# MyNixie.net
KiCad netlist of a schematic drawn in Altium Designer
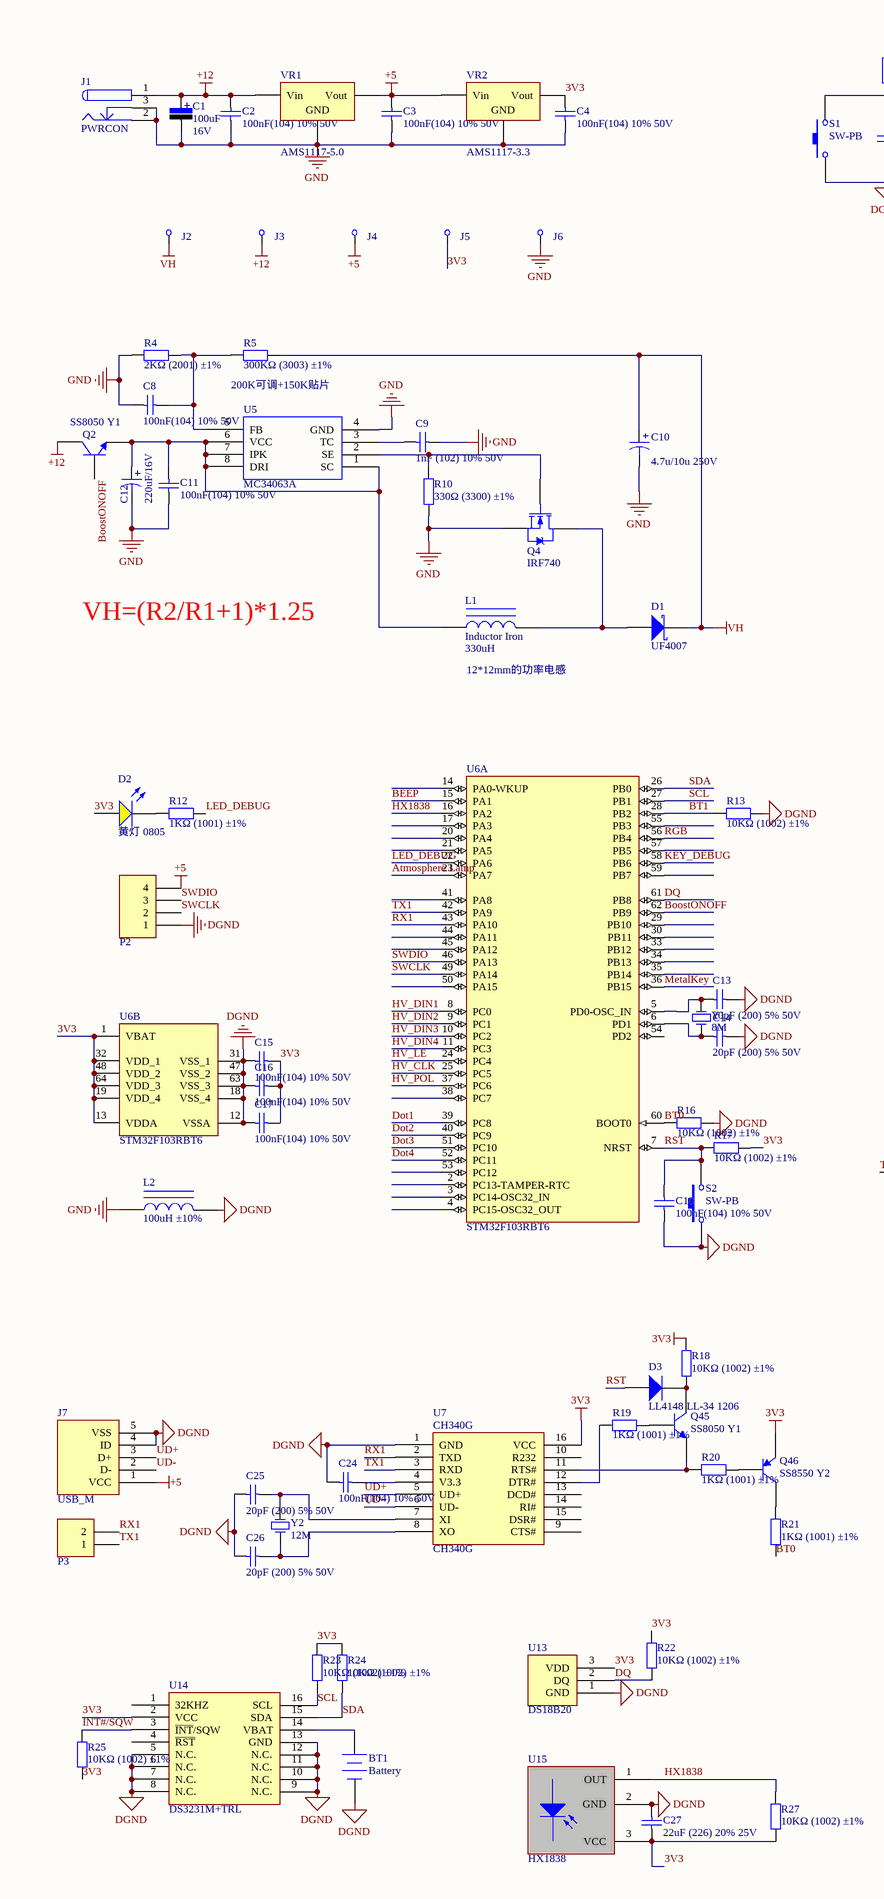
[diagram p0: MyNixie.SchDoc, left]
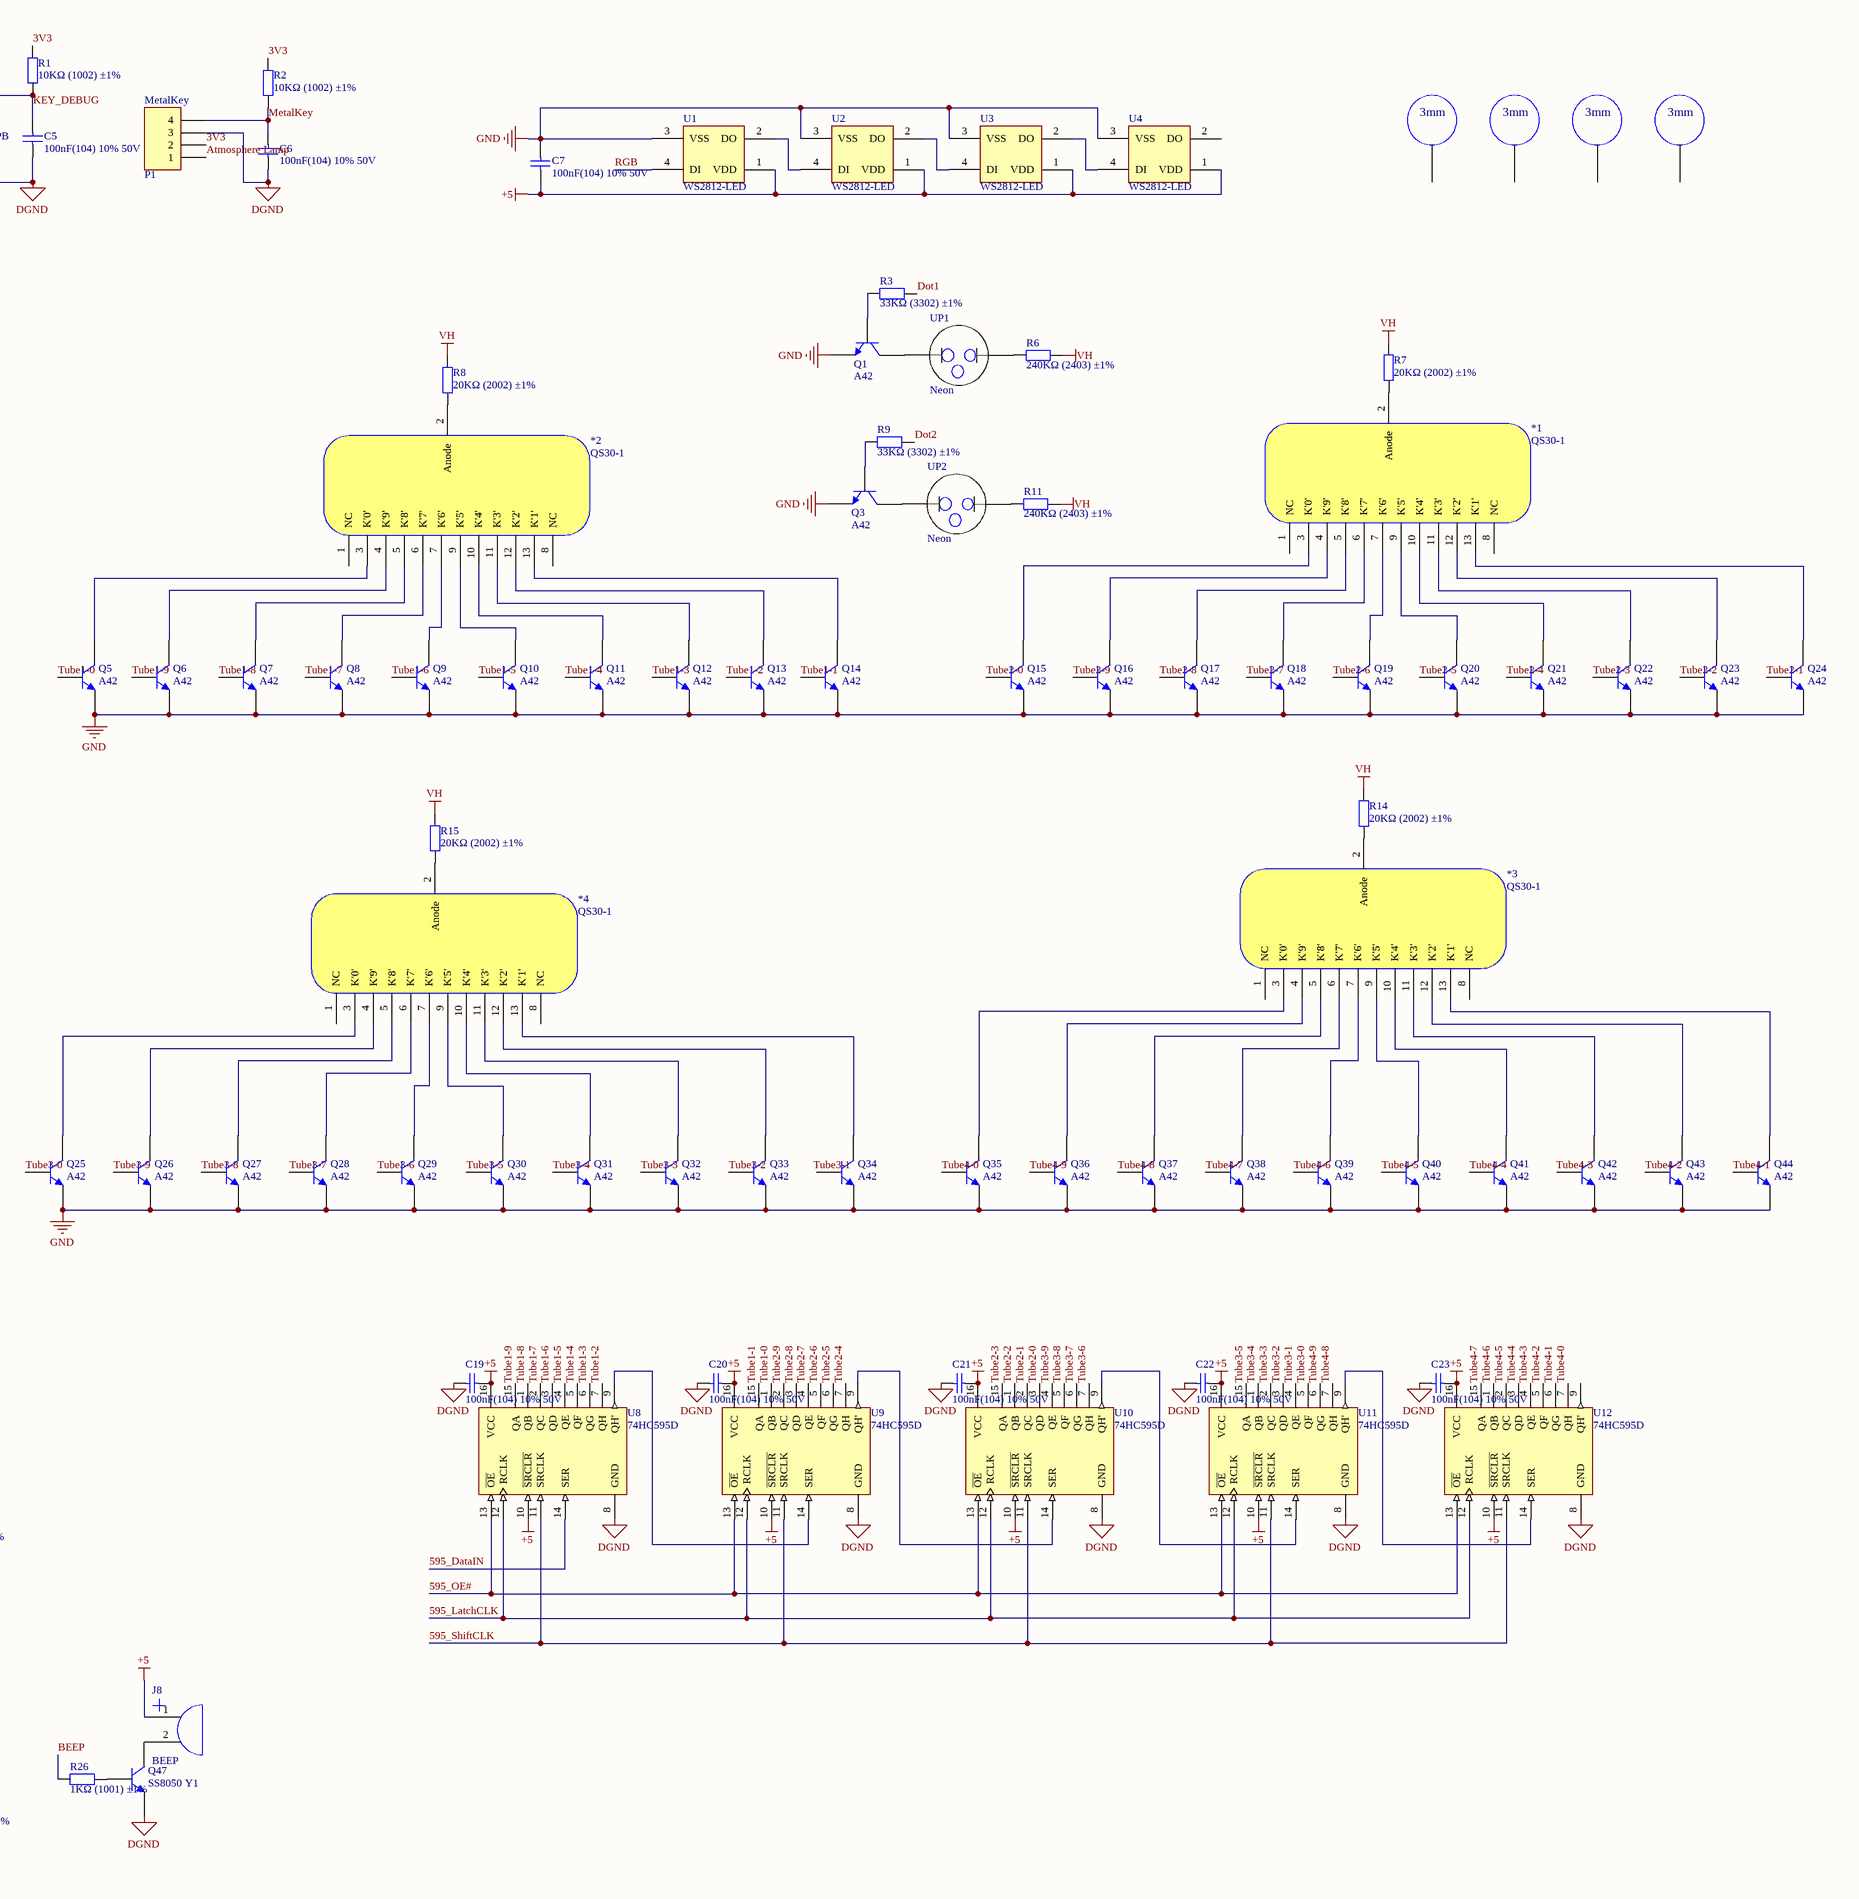
[diagram p1: MyNixie.SchDoc, right]

(export (version "E")
  (design (tool "Eeschema 10.0.6"))
  (components
    (comp (ref "*1")
      (value "QS30-1")
      (footprint "QS30-1")
      (description "南昌辉光管")
      (libsource (lib "fszhang") (part "QS30-1"))
    )
    (comp (ref "*2")
      (value "QS30-1")
      (footprint "QS30-1")
      (description "南昌辉光管")
      (libsource (lib "fszhang") (part "QS30-1"))
    )
    (comp (ref "*3")
      (value "QS30-1")
      (footprint "QS30-1")
      (description "南昌辉光管")
      (libsource (lib "fszhang") (part "QS30-1"))
    )
    (comp (ref "*4")
      (value "QS30-1")
      (footprint "QS30-1")
      (description "南昌辉光管")
      (libsource (lib "fszhang") (part "QS30-1"))
    )
    (comp (ref "BT1")
      (value "Battery")
      (footprint "CR1220")
      (description "备份电池")
      (fields (field (name "PUBLISHER") "Altium Limited"))
      (libsource (lib "fszhang") (part "Battery"))
    )
    (comp (ref "C1")
      (value "100uF")
      (footprint "C-RB-10")
      (description "极性电解电容")
      (fields
        (field (name "VOL") "16V")
        (field (name "Comment") "Cap Pol")
        (field (name "PUBLISHER") "Altium Limited")
      )
      (libsource (lib "fszhang") (part "Cap Pol"))
    )
    (comp (ref "C2")
      (value "100nF(104) 10% 50V")
      (footprint "LC-0805_C")
      (description "贴片电容")
      (libsource (lib "Miscellaneous Devices LC") (part "0805 100nF(104) 10% 50V"))
    )
    (comp (ref "C3")
      (value "100nF(104) 10% 50V")
      (footprint "LC-0805_C")
      (description "贴片电容")
      (libsource (lib "Miscellaneous Devices LC") (part "0805 100nF(104) 10% 50V"))
    )
    (comp (ref "C4")
      (value "100nF(104) 10% 50V")
      (footprint "LC-0805_C")
      (description "贴片电容")
      (libsource (lib "Miscellaneous Devices LC") (part "0805 100nF(104) 10% 50V"))
    )
    (comp (ref "C5")
      (value "100nF(104) 10% 50V")
      (footprint "LC-0805_C")
      (description "贴片电容")
      (libsource (lib "Miscellaneous Devices LC") (part "0805 100nF(104) 10% 50V"))
    )
    (comp (ref "C6")
      (value "100nF(104) 10% 50V")
      (footprint "LC-0805_C")
      (description "贴片电容")
      (libsource (lib "Miscellaneous Devices LC") (part "0805 100nF(104) 10% 50V"))
    )
    (comp (ref "C7")
      (value "100nF(104) 10% 50V")
      (footprint "LC-0805_C")
      (description "贴片电容")
      (libsource (lib "Miscellaneous Devices LC") (part "0805 100nF(104) 10% 50V"))
    )
    (comp (ref "C8")
      (value "100nF(104) 10% 50V")
      (footprint "LC-0805_C")
      (description "贴片电容")
      (libsource (lib "Miscellaneous Devices LC") (part "0805 100nF(104) 10% 50V"))
    )
    (comp (ref "C9")
      (value "1nF (102) 10% 50V")
      (footprint "LC-0805_C")
      (description "贴片电容")
      (libsource (lib "Miscellaneous Devices LC") (part "0805 1nF (102) 10% 50V"))
    )
    (comp (ref "C10")
      (value "4.7u/10u 250V")
      (footprint "C-RB-10")
      (description "Polarized Capacitor (Radial)")
      (fields (field (name "Comment") "Cap Pol1") (field (name "PUBLISHER") "Altium Limited"))
      (libsource (lib "Miscellaneous Devices") (part "Cap Pol1"))
    )
    (comp (ref "C11")
      (value "100nF(104) 10% 50V")
      (footprint "LC-0805_C")
      (description "贴片电容")
      (libsource (lib "Miscellaneous Devices LC") (part "0805 100nF(104) 10% 50V"))
    )
    (comp (ref "C12")
      (value "220uF/16V")
      (footprint "C-RB-6")
      (description "Polarized Capacitor (Radial)")
      (fields (field (name "Comment") "Cap Pol1") (field (name "PUBLISHER") "Altium Limited"))
      (libsource (lib "Miscellaneous Devices") (part "Cap Pol1"))
    )
    (comp (ref "C13")
      (value "20pF (200) 5% 50V")
      (footprint "LC-0805_C")
      (description "贴片电容")
      (libsource (lib "Miscellaneous Devices LC") (part "0805 20pF (200) 5% 50V"))
    )
    (comp (ref "C14")
      (value "20pF (200) 5% 50V")
      (footprint "LC-0805_C")
      (description "贴片电容")
      (libsource (lib "Miscellaneous Devices LC") (part "0805 20pF (200) 5% 50V"))
    )
    (comp (ref "C15")
      (value "100nF(104) 10% 50V")
      (footprint "LC-0805_C")
      (description "贴片电容")
      (libsource (lib "Miscellaneous Devices LC") (part "0805 100nF(104) 10% 50V"))
    )
    (comp (ref "C16")
      (value "100nF(104) 10% 50V")
      (footprint "LC-0805_C")
      (description "贴片电容")
      (libsource (lib "Miscellaneous Devices LC") (part "0805 100nF(104) 10% 50V"))
    )
    (comp (ref "C17")
      (value "100nF(104) 10% 50V")
      (footprint "LC-0805_C")
      (description "贴片电容")
      (libsource (lib "Miscellaneous Devices LC") (part "0805 100nF(104) 10% 50V"))
    )
    (comp (ref "C18")
      (value "100nF(104) 10% 50V")
      (footprint "LC-0805_C")
      (description "贴片电容")
      (libsource (lib "Miscellaneous Devices LC") (part "0805 100nF(104) 10% 50V"))
    )
    (comp (ref "C19")
      (value "100nF(104) 10% 50V")
      (footprint "LC-0805_C")
      (description "贴片电容")
      (libsource (lib "Miscellaneous Devices LC") (part "0805 100nF(104) 10% 50V"))
    )
    (comp (ref "C20")
      (value "100nF(104) 10% 50V")
      (footprint "LC-0805_C")
      (description "贴片电容")
      (libsource (lib "Miscellaneous Devices LC") (part "0805 100nF(104) 10% 50V"))
    )
    (comp (ref "C21")
      (value "100nF(104) 10% 50V")
      (footprint "LC-0805_C")
      (description "贴片电容")
      (libsource (lib "Miscellaneous Devices LC") (part "0805 100nF(104) 10% 50V"))
    )
    (comp (ref "C22")
      (value "100nF(104) 10% 50V")
      (footprint "LC-0805_C")
      (description "贴片电容")
      (libsource (lib "Miscellaneous Devices LC") (part "0805 100nF(104) 10% 50V"))
    )
    (comp (ref "C23")
      (value "100nF(104) 10% 50V")
      (footprint "LC-0805_C")
      (description "贴片电容")
      (libsource (lib "Miscellaneous Devices LC") (part "0805 100nF(104) 10% 50V"))
    )
    (comp (ref "C24")
      (value "100nF(104) 10% 50V")
      (footprint "LC-0805_C")
      (description "贴片电容")
      (libsource (lib "Miscellaneous Devices LC") (part "0805 100nF(104) 10% 50V"))
    )
    (comp (ref "C25")
      (value "20pF (200) 5% 50V")
      (footprint "LC-0805_C")
      (description "贴片电容")
      (libsource (lib "Miscellaneous Devices LC") (part "0805 20pF (200) 5% 50V"))
    )
    (comp (ref "C26")
      (value "20pF (200) 5% 50V")
      (footprint "LC-0805_C")
      (description "贴片电容")
      (libsource (lib "Miscellaneous Devices LC") (part "0805 20pF (200) 5% 50V"))
    )
    (comp (ref "C27")
      (value "22uF (226) 20% 25V")
      (footprint "LC-0805_C")
      (description "贴片电容")
      (libsource (lib "Miscellaneous Devices LC") (part "0805 22uF (226) 20% 25V"))
    )
    (comp (ref "D1")
      (value "UF4007")
      (footprint "DO-41")
      (description "Schottky Diode")
      (fields (field (name "PUBLISHER") "Altium Limited"))
      (libsource (lib "Miscellaneous Devices") (part "D Schottky"))
    )
    (comp (ref "D2")
      (value "黄灯 0805")
      (footprint "LC-0805_LED_S1")
      (description "发光二极管")
      (libsource (lib "Miscellaneous Devices LC") (part "0805 黄灯"))
    )
    (comp (ref "D3")
      (value "LL4148 LL-34 1206")
      (footprint "LC-LL-34")
      (description "开关二极管")
      (libsource (lib "Miscellaneous Devices LC") (part "LL-34 LL4148 LL-34 1206"))
    )
    (comp (ref "J1")
      (value "PWRCON")
      (footprint "DC-005")
      (description "直流电源端子")
      (fields (field (name "PUBLISHER") "Altium Limited"))
      (libsource (lib "fszhang") (part "PWRCON"))
    )
    (comp (ref "J2")
      (value "CHECK")
      (footprint "CHECK-A")
      (description "测试点")
      (libsource (lib "fszhang") (part "CHECK"))
    )
    (comp (ref "J3")
      (value "CHECK")
      (footprint "CHECK-A")
      (description "测试点")
      (libsource (lib "fszhang") (part "CHECK"))
    )
    (comp (ref "J4")
      (value "CHECK")
      (footprint "CHECK-A")
      (description "测试点")
      (libsource (lib "fszhang") (part "CHECK"))
    )
    (comp (ref "J5")
      (value "CHECK")
      (footprint "CHECK-A")
      (description "测试点")
      (libsource (lib "fszhang") (part "CHECK"))
    )
    (comp (ref "J6")
      (value "CHECK")
      (footprint "CHECK-A")
      (description "测试点")
      (libsource (lib "fszhang") (part "CHECK"))
    )
    (comp (ref "J7")
      (value "USB_M")
      (footprint "USB_MICRO")
      (description "MicroUSB接口")
      (libsource (lib "fszhang") (part "USB_M"))
    )
    (comp (ref "J8")
      (value "BEEP")
      (footprint "Beep")
      (description "蜂鸣器")
      (libsource (lib "fszhang") (part "BEEP"))
    )
    (comp (ref "L1")
      (value "Inductor Iron")
      (footprint "L-SMD-12")
      (description "Magnetic-Core Inductor")
      (fields (field (name "ALTIUM_VALUE") "330uH") (field (name "PUBLISHER") "Altium Limited"))
      (libsource (lib "Miscellaneous Devices") (part "Inductor Iron"))
    )
    (comp (ref "L2")
      (value "100uH ±10%")
      (footprint "LC-0805_L")
      (description "贴片电感")
      (libsource (lib "Miscellaneous Devices LC") (part "0805 100uH 10%"))
    )
    (comp (ref "P1")
      (value "MetalKey")
      (footprint "HDR4X1_A")
      (description "接插件")
      (fields (field (name "PUBLISHER") "Altium Limited"))
      (libsource (lib "fszhang") (part "Header 4"))
    )
    (comp (ref "P2")
      (value "Header 4")
      (footprint "HDR4X1_A")
      (description "接插件")
      (fields (field (name "PUBLISHER") "Altium Limited"))
      (libsource (lib "fszhang") (part "Header 4"))
    )
    (comp (ref "P3")
      (value "Header 2")
      (footprint "HDR2X1_A")
      (description "接插件")
      (fields (field (name "PUBLISHER") "Altium Limited"))
      (libsource (lib "fszhang") (part "Header 2"))
    )
    (comp (ref "Q1")
      (value "A42")
      (footprint "LC-SOT-23(SOT-23-3)")
      (description "三极管")
      (libsource (lib "Miscellaneous Devices LC") (part "SOT-23 SS8050 Y1"))
    )
    (comp (ref "Q2")
      (value "SS8050 Y1")
      (footprint "LC-SOT-23(SOT-23-3)")
      (description "三极管")
      (libsource (lib "Miscellaneous Devices LC") (part "SOT-23 SS8050 Y1"))
    )
    (comp (ref "Q3")
      (value "A42")
      (footprint "LC-SOT-23(SOT-23-3)")
      (description "三极管")
      (libsource (lib "Miscellaneous Devices LC") (part "SOT-23 SS8050 Y1"))
    )
    (comp (ref "Q4")
      (value "IRF740")
      (footprint "TO-220AB")
      (description "N-Channel Power MOSFET")
      (fields (field (name "PUBLISHER") "Altium Limited"))
      (libsource (lib "Miscellaneous Devices") (part "NMOS-2"))
    )
    (comp (ref "Q5")
      (value "A42")
      (footprint "LC-SOT-23(SOT-23-3)")
      (description "三极管")
      (libsource (lib "Miscellaneous Devices LC") (part "SOT-23 SS8050 Y1"))
    )
    (comp (ref "Q6")
      (value "A42")
      (footprint "LC-SOT-23(SOT-23-3)")
      (description "三极管")
      (libsource (lib "Miscellaneous Devices LC") (part "SOT-23 SS8050 Y1"))
    )
    (comp (ref "Q7")
      (value "A42")
      (footprint "LC-SOT-23(SOT-23-3)")
      (description "三极管")
      (libsource (lib "Miscellaneous Devices LC") (part "SOT-23 SS8050 Y1"))
    )
    (comp (ref "Q8")
      (value "A42")
      (footprint "LC-SOT-23(SOT-23-3)")
      (description "三极管")
      (libsource (lib "Miscellaneous Devices LC") (part "SOT-23 SS8050 Y1"))
    )
    (comp (ref "Q9")
      (value "A42")
      (footprint "LC-SOT-23(SOT-23-3)")
      (description "三极管")
      (libsource (lib "Miscellaneous Devices LC") (part "SOT-23 SS8050 Y1"))
    )
    (comp (ref "Q10")
      (value "A42")
      (footprint "LC-SOT-23(SOT-23-3)")
      (description "三极管")
      (libsource (lib "Miscellaneous Devices LC") (part "SOT-23 SS8050 Y1"))
    )
    (comp (ref "Q11")
      (value "A42")
      (footprint "LC-SOT-23(SOT-23-3)")
      (description "三极管")
      (libsource (lib "Miscellaneous Devices LC") (part "SOT-23 SS8050 Y1"))
    )
    (comp (ref "Q12")
      (value "A42")
      (footprint "LC-SOT-23(SOT-23-3)")
      (description "三极管")
      (libsource (lib "Miscellaneous Devices LC") (part "SOT-23 SS8050 Y1"))
    )
    (comp (ref "Q13")
      (value "A42")
      (footprint "LC-SOT-23(SOT-23-3)")
      (description "三极管")
      (libsource (lib "Miscellaneous Devices LC") (part "SOT-23 SS8050 Y1"))
    )
    (comp (ref "Q14")
      (value "A42")
      (footprint "LC-SOT-23(SOT-23-3)")
      (description "三极管")
      (libsource (lib "Miscellaneous Devices LC") (part "SOT-23 SS8050 Y1"))
    )
    (comp (ref "Q15")
      (value "A42")
      (footprint "LC-SOT-23(SOT-23-3)")
      (description "三极管")
      (libsource (lib "Miscellaneous Devices LC") (part "SOT-23 SS8050 Y1"))
    )
    (comp (ref "Q16")
      (value "A42")
      (footprint "LC-SOT-23(SOT-23-3)")
      (description "三极管")
      (libsource (lib "Miscellaneous Devices LC") (part "SOT-23 SS8050 Y1"))
    )
    (comp (ref "Q17")
      (value "A42")
      (footprint "LC-SOT-23(SOT-23-3)")
      (description "三极管")
      (libsource (lib "Miscellaneous Devices LC") (part "SOT-23 SS8050 Y1"))
    )
    (comp (ref "Q18")
      (value "A42")
      (footprint "LC-SOT-23(SOT-23-3)")
      (description "三极管")
      (libsource (lib "Miscellaneous Devices LC") (part "SOT-23 SS8050 Y1"))
    )
    (comp (ref "Q19")
      (value "A42")
      (footprint "LC-SOT-23(SOT-23-3)")
      (description "三极管")
      (libsource (lib "Miscellaneous Devices LC") (part "SOT-23 SS8050 Y1"))
    )
    (comp (ref "Q20")
      (value "A42")
      (footprint "LC-SOT-23(SOT-23-3)")
      (description "三极管")
      (libsource (lib "Miscellaneous Devices LC") (part "SOT-23 SS8050 Y1"))
    )
    (comp (ref "Q21")
      (value "A42")
      (footprint "LC-SOT-23(SOT-23-3)")
      (description "三极管")
      (libsource (lib "Miscellaneous Devices LC") (part "SOT-23 SS8050 Y1"))
    )
    (comp (ref "Q22")
      (value "A42")
      (footprint "LC-SOT-23(SOT-23-3)")
      (description "三极管")
      (libsource (lib "Miscellaneous Devices LC") (part "SOT-23 SS8050 Y1"))
    )
    (comp (ref "Q23")
      (value "A42")
      (footprint "LC-SOT-23(SOT-23-3)")
      (description "三极管")
      (libsource (lib "Miscellaneous Devices LC") (part "SOT-23 SS8050 Y1"))
    )
    (comp (ref "Q24")
      (value "A42")
      (footprint "LC-SOT-23(SOT-23-3)")
      (description "三极管")
      (libsource (lib "Miscellaneous Devices LC") (part "SOT-23 SS8050 Y1"))
    )
    (comp (ref "Q25")
      (value "A42")
      (footprint "LC-SOT-23(SOT-23-3)")
      (description "三极管")
      (libsource (lib "Miscellaneous Devices LC") (part "SOT-23 SS8050 Y1"))
    )
    (comp (ref "Q26")
      (value "A42")
      (footprint "LC-SOT-23(SOT-23-3)")
      (description "三极管")
      (libsource (lib "Miscellaneous Devices LC") (part "SOT-23 SS8050 Y1"))
    )
    (comp (ref "Q27")
      (value "A42")
      (footprint "LC-SOT-23(SOT-23-3)")
      (description "三极管")
      (libsource (lib "Miscellaneous Devices LC") (part "SOT-23 SS8050 Y1"))
    )
    (comp (ref "Q28")
      (value "A42")
      (footprint "LC-SOT-23(SOT-23-3)")
      (description "三极管")
      (libsource (lib "Miscellaneous Devices LC") (part "SOT-23 SS8050 Y1"))
    )
    (comp (ref "Q29")
      (value "A42")
      (footprint "LC-SOT-23(SOT-23-3)")
      (description "三极管")
      (libsource (lib "Miscellaneous Devices LC") (part "SOT-23 SS8050 Y1"))
    )
    (comp (ref "Q30")
      (value "A42")
      (footprint "LC-SOT-23(SOT-23-3)")
      (description "三极管")
      (libsource (lib "Miscellaneous Devices LC") (part "SOT-23 SS8050 Y1"))
    )
    (comp (ref "Q31")
      (value "A42")
      (footprint "LC-SOT-23(SOT-23-3)")
      (description "三极管")
      (libsource (lib "Miscellaneous Devices LC") (part "SOT-23 SS8050 Y1"))
    )
    (comp (ref "Q32")
      (value "A42")
      (footprint "LC-SOT-23(SOT-23-3)")
      (description "三极管")
      (libsource (lib "Miscellaneous Devices LC") (part "SOT-23 SS8050 Y1"))
    )
    (comp (ref "Q33")
      (value "A42")
      (footprint "LC-SOT-23(SOT-23-3)")
      (description "三极管")
      (libsource (lib "Miscellaneous Devices LC") (part "SOT-23 SS8050 Y1"))
    )
    (comp (ref "Q34")
      (value "A42")
      (footprint "LC-SOT-23(SOT-23-3)")
      (description "三极管")
      (libsource (lib "Miscellaneous Devices LC") (part "SOT-23 SS8050 Y1"))
    )
    (comp (ref "Q35")
      (value "A42")
      (footprint "LC-SOT-23(SOT-23-3)")
      (description "三极管")
      (libsource (lib "Miscellaneous Devices LC") (part "SOT-23 SS8050 Y1"))
    )
    (comp (ref "Q36")
      (value "A42")
      (footprint "LC-SOT-23(SOT-23-3)")
      (description "三极管")
      (libsource (lib "Miscellaneous Devices LC") (part "SOT-23 SS8050 Y1"))
    )
    (comp (ref "Q37")
      (value "A42")
      (footprint "LC-SOT-23(SOT-23-3)")
      (description "三极管")
      (libsource (lib "Miscellaneous Devices LC") (part "SOT-23 SS8050 Y1"))
    )
    (comp (ref "Q38")
      (value "A42")
      (footprint "LC-SOT-23(SOT-23-3)")
      (description "三极管")
      (libsource (lib "Miscellaneous Devices LC") (part "SOT-23 SS8050 Y1"))
    )
    (comp (ref "Q39")
      (value "A42")
      (footprint "LC-SOT-23(SOT-23-3)")
      (description "三极管")
      (libsource (lib "Miscellaneous Devices LC") (part "SOT-23 SS8050 Y1"))
    )
    (comp (ref "Q40")
      (value "A42")
      (footprint "LC-SOT-23(SOT-23-3)")
      (description "三极管")
      (libsource (lib "Miscellaneous Devices LC") (part "SOT-23 SS8050 Y1"))
    )
    (comp (ref "Q41")
      (value "A42")
      (footprint "LC-SOT-23(SOT-23-3)")
      (description "三极管")
      (libsource (lib "Miscellaneous Devices LC") (part "SOT-23 SS8050 Y1"))
    )
    (comp (ref "Q42")
      (value "A42")
      (footprint "LC-SOT-23(SOT-23-3)")
      (description "三极管")
      (libsource (lib "Miscellaneous Devices LC") (part "SOT-23 SS8050 Y1"))
    )
    (comp (ref "Q43")
      (value "A42")
      (footprint "LC-SOT-23(SOT-23-3)")
      (description "三极管")
      (libsource (lib "Miscellaneous Devices LC") (part "SOT-23 SS8050 Y1"))
    )
    (comp (ref "Q44")
      (value "A42")
      (footprint "LC-SOT-23(SOT-23-3)")
      (description "三极管")
      (libsource (lib "Miscellaneous Devices LC") (part "SOT-23 SS8050 Y1"))
    )
    (comp (ref "Q45")
      (value "SS8050 Y1")
      (footprint "LC-SOT-23(SOT-23-3)")
      (description "三极管")
      (libsource (lib "Miscellaneous Devices LC") (part "SOT-23 SS8050 Y1"))
    )
    (comp (ref "Q46")
      (value "SS8550 Y2")
      (footprint "LC-SOT-23(SOT-23-3)")
      (description "三极管")
      (libsource (lib "Miscellaneous Devices LC") (part "SOT-23 SS8550 Y2"))
    )
    (comp (ref "Q47")
      (value "SS8050 Y1")
      (footprint "LC-SOT-23(SOT-23-3)")
      (description "三极管")
      (libsource (lib "Miscellaneous Devices LC") (part "SOT-23 SS8050 Y1"))
    )
    (comp (ref "R1")
      (value "10KΩ (1002) ±1%")
      (footprint "LC-0805_R")
      (description "贴片电阻")
      (libsource (lib "") (part "0805 10KΩ (1002) 1%_1"))
    )
    (comp (ref "R2")
      (value "10KΩ (1002) ±1%")
      (footprint "LC-0805_R")
      (description "贴片电阻")
      (libsource (lib "") (part "0805 10KΩ (1002) 1%_1"))
    )
    (comp (ref "R3")
      (value "33KΩ (3302) ±1%")
      (footprint "LC-0805_R")
      (description "贴片电阻")
      (libsource (lib "") (part "0805 33KΩ (3302) 1%_1"))
    )
    (comp (ref "R4")
      (value "2KΩ (2001) ±1%")
      (footprint "LC-0805_R")
      (description "贴片电阻")
      (libsource (lib "Miscellaneous Devices LC") (part "0805 2KΩ (2001) 1%"))
    )
    (comp (ref "R5")
      (value "300KΩ (3003) ±1%")
      (footprint "LC-0805_R")
      (description "贴片电阻")
      (libsource (lib "Miscellaneous Devices LC") (part "0805 300KΩ (3003) 1%"))
    )
    (comp (ref "R6")
      (value "240KΩ (2403) ±1%")
      (footprint "LC-0805_R")
      (description "贴片电阻")
      (libsource (lib "Miscellaneous Devices LC") (part "0805 240KΩ (2403) 1%"))
    )
    (comp (ref "R7")
      (value "20KΩ (2002) ±1%")
      (footprint "LC-0805_R")
      (description "贴片电阻")
      (libsource (lib "Miscellaneous Devices LC") (part "0805 20KΩ (2002) 1%"))
    )
    (comp (ref "R8")
      (value "20KΩ (2002) ±1%")
      (footprint "LC-0805_R")
      (description "贴片电阻")
      (libsource (lib "Miscellaneous Devices LC") (part "0805 20KΩ (2002) 1%"))
    )
    (comp (ref "R9")
      (value "33KΩ (3302) ±1%")
      (footprint "LC-0805_R")
      (description "贴片电阻")
      (libsource (lib "Miscellaneous Devices LC") (part "0805 33KΩ (3302) 1%"))
    )
    (comp (ref "R10")
      (value "330Ω (3300) ±1%")
      (footprint "LC-0805_R")
      (description "贴片电阻")
      (libsource (lib "Miscellaneous Devices LC") (part "0805 330Ω (3300) 1%"))
    )
    (comp (ref "R11")
      (value "240KΩ (2403) ±1%")
      (footprint "LC-0805_R")
      (description "贴片电阻")
      (libsource (lib "Miscellaneous Devices LC") (part "0805 240KΩ (2403) 1%"))
    )
    (comp (ref "R12")
      (value "1KΩ (1001) ±1%")
      (footprint "LC-0805_R")
      (description "贴片电阻")
      (libsource (lib "Miscellaneous Devices LC") (part "0805 1KΩ (1001) 1%"))
    )
    (comp (ref "R13")
      (value "10KΩ (1002) ±1%")
      (footprint "LC-0805_R")
      (description "贴片电阻")
      (libsource (lib "Miscellaneous Devices LC") (part "0805 10KΩ (1002) 1%"))
    )
    (comp (ref "R14")
      (value "20KΩ (2002) ±1%")
      (footprint "LC-0805_R")
      (description "贴片电阻")
      (libsource (lib "Miscellaneous Devices LC") (part "0805 20KΩ (2002) 1%"))
    )
    (comp (ref "R15")
      (value "20KΩ (2002) ±1%")
      (footprint "LC-0805_R")
      (description "贴片电阻")
      (libsource (lib "Miscellaneous Devices LC") (part "0805 20KΩ (2002) 1%"))
    )
    (comp (ref "R16")
      (value "10KΩ (1002) ±1%")
      (footprint "LC-0805_R")
      (description "贴片电阻")
      (libsource (lib "Miscellaneous Devices LC") (part "0805 10KΩ (1002) 1%"))
    )
    (comp (ref "R17")
      (value "10KΩ (1002) ±1%")
      (footprint "LC-0805_R")
      (description "贴片电阻")
      (libsource (lib "Miscellaneous Devices LC") (part "0805 10KΩ (1002) 1%"))
    )
    (comp (ref "R18")
      (value "10KΩ (1002) ±1%")
      (footprint "LC-0805_R")
      (description "贴片电阻")
      (libsource (lib "") (part "0805 10KΩ (1002) 1%_2"))
    )
    (comp (ref "R19")
      (value "1KΩ (1001) ±1%")
      (footprint "LC-0805_R")
      (description "贴片电阻")
      (libsource (lib "Miscellaneous Devices LC") (part "0805 1KΩ (1001) 1%"))
    )
    (comp (ref "R20")
      (value "1KΩ (1001) ±1%")
      (footprint "LC-0805_R")
      (description "贴片电阻")
      (libsource (lib "Miscellaneous Devices LC") (part "0805 1KΩ (1001) 1%"))
    )
    (comp (ref "R21")
      (value "1KΩ (1001) ±1%")
      (footprint "LC-0805_R")
      (description "贴片电阻")
      (libsource (lib "") (part "0805 1KΩ (1001) 1%_1"))
    )
    (comp (ref "R22")
      (value "10KΩ (1002) ±1%")
      (footprint "LC-0805_R")
      (description "贴片电阻")
      (libsource (lib "Miscellaneous Devices LC") (part "0805 10KΩ (1002) 1%"))
    )
    (comp (ref "R23")
      (value "10KΩ (1002) ±1%")
      (footprint "LC-0805_R")
      (description "贴片电阻")
      (libsource (lib "Miscellaneous Devices LC") (part "0805 10KΩ (1002) 1%"))
    )
    (comp (ref "R24")
      (value "10KΩ (1002) ±1%")
      (footprint "LC-0805_R")
      (description "贴片电阻")
      (libsource (lib "Miscellaneous Devices LC") (part "0805 10KΩ (1002) 1%"))
    )
    (comp (ref "R25")
      (value "10KΩ (1002) ±1%")
      (footprint "LC-0805_R")
      (description "贴片电阻")
      (libsource (lib "Miscellaneous Devices LC") (part "0805 10KΩ (1002) 1%"))
    )
    (comp (ref "R26")
      (value "1KΩ (1001) ±1%")
      (footprint "LC-0805_R")
      (description "贴片电阻")
      (libsource (lib "Miscellaneous Devices LC") (part "0805 1KΩ (1001) 1%"))
    )
    (comp (ref "R27")
      (value "10KΩ (1002) ±1%")
      (footprint "LC-0805_R")
      (description "贴片电阻")
      (libsource (lib "Miscellaneous Devices LC") (part "0805 10KΩ (1002) 1%"))
    )
    (comp (ref "S1")
      (value "SW-PB")
      (footprint "SW_PB2_A1")
      (description "微动开关")
      (fields (field (name "PUBLISHER") "Altium Limited"))
      (libsource (lib "fszhang") (part "SW-PB"))
    )
    (comp (ref "S2")
      (value "SW-PB")
      (footprint "SW_PB2_A1")
      (description "微动开关")
      (fields (field (name "PUBLISHER") "Altium Limited"))
      (libsource (lib "fszhang") (part "SW-PB"))
    )
    (comp (ref "T1") (value "M3铜柱螺丝孔") (footprint "螺丝孔-3mm") (libsource (lib "fszhang") (part "M3铜柱螺丝孔")))
    (comp (ref "T2") (value "M3铜柱螺丝孔") (footprint "螺丝孔-3mm") (libsource (lib "fszhang") (part "M3铜柱螺丝孔")))
    (comp (ref "T3") (value "M3铜柱螺丝孔") (footprint "螺丝孔-3mm") (libsource (lib "fszhang") (part "M3铜柱螺丝孔")))
    (comp (ref "T4") (value "M3铜柱螺丝孔") (footprint "螺丝孔-3mm") (libsource (lib "fszhang") (part "M3铜柱螺丝孔")))
    (comp (ref "U1")
      (value "WS2812-LED")
      (footprint "WS2812")
      (libsource (lib "fszhang") (part "WS2812-LED"))
    )
    (comp (ref "U2")
      (value "WS2812-LED")
      (footprint "WS2812")
      (libsource (lib "fszhang") (part "WS2812-LED"))
    )
    (comp (ref "U3")
      (value "WS2812-LED")
      (footprint "WS2812")
      (libsource (lib "fszhang") (part "WS2812-LED"))
    )
    (comp (ref "U4")
      (value "WS2812-LED")
      (footprint "WS2812")
      (libsource (lib "fszhang") (part "WS2812-LED"))
    )
    (comp (ref "U5")
      (value "MC34063A")
      (footprint "LC-SOIC-8_150mil")
      (libsource (lib "NIXIEClock_SCHLib") (part "MC34063A"))
    )
    (comp (ref "U6")
      (value "STM32F103RBT6")
      (footprint "LC-LQFP-64_10x10x05P")
      (description "ARM")
      (libsource (lib "Miscellaneous Devices LC") (part "STM32F103RBT6"))
    )
    (comp (ref "U7")
      (value "CH340G")
      (footprint "LC-SOIC-16_150mil")
      (description "USB")
      (libsource (lib "Miscellaneous Devices LC") (part "CH340G"))
    )
    (comp (ref "U8")
      (value "74HC595D")
      (footprint "LC-SOIC-16_150mil")
      (description "74系列逻辑芯片")
      (libsource (lib "Miscellaneous Devices LC") (part "74HC595D"))
    )
    (comp (ref "U9")
      (value "74HC595D")
      (footprint "LC-SOIC-16_150mil")
      (description "74系列逻辑芯片")
      (libsource (lib "Miscellaneous Devices LC") (part "74HC595D"))
    )
    (comp (ref "U10")
      (value "74HC595D")
      (footprint "LC-SOIC-16_150mil")
      (description "74系列逻辑芯片")
      (libsource (lib "Miscellaneous Devices LC") (part "74HC595D"))
    )
    (comp (ref "U11")
      (value "74HC595D")
      (footprint "LC-SOIC-16_150mil")
      (description "74系列逻辑芯片")
      (libsource (lib "Miscellaneous Devices LC") (part "74HC595D"))
    )
    (comp (ref "U12")
      (value "74HC595D")
      (footprint "LC-SOIC-16_150mil")
      (description "74系列逻辑芯片")
      (libsource (lib "Miscellaneous Devices LC") (part "74HC595D"))
    )
    (comp (ref "U13")
      (value "DS18B20")
      (footprint "TO-92A")
      (description "温度传感器")
      (libsource (lib "fszhang") (part "DS18B20"))
    )
    (comp (ref "U14")
      (value "DS3231M+TRL")
      (footprint "LC-SOIC-16_300mil")
      (description "实时时钟")
      (libsource (lib "Miscellaneous Devices LC") (part "DS3231M+TRL"))
    )
    (comp (ref "U15")
      (value "HX1838")
      (footprint "HS0038B")
      (description "红外接收器")
      (libsource (lib "fszhang") (part "HS0038B"))
    )
    (comp (ref "UP1") (value "Neon") (description "氖泡") (libsource (lib "fszhang") (part "Neon")))
    (comp (ref "UP2") (value "Neon") (description "氖泡") (libsource (lib "fszhang") (part "Neon")))
    (comp (ref "VR1")
      (value "AMS1117-5.0")
      (footprint "LC-SOT-223")
      (description "低压差线性稳压(LDO)")
      (libsource (lib "Miscellaneous Devices LC") (part "SOT-223 AMS1117-5.0"))
    )
    (comp (ref "VR2")
      (value "AMS1117-3.3")
      (footprint "LC-SOT-223")
      (description "低压差线性稳压(LDO)")
      (libsource (lib "Miscellaneous Devices LC") (part "SOT-223 AMS1117-3.3"))
    )
    (comp (ref "Y1")
      (value "8M")
      (footprint "X-HC49U")
      (description "晶振")
      (fields (field (name "Comment") "XTAL") (field (name "PUBLISHER") "Altium Limited"))
      (libsource (lib "fszhang") (part "XTAL"))
    )
    (comp (ref "Y2")
      (value "12M")
      (footprint "X-HC49U")
      (description "晶振")
      (fields (field (name "Comment") "XTAL") (field (name "PUBLISHER") "Altium Limited"))
      (libsource (lib "fszhang") (part "XTAL"))
    )
  )
  (nets
    (net (code "1") (name "+5") (class "Default")
      (node (ref "C19") (pin "1") (pinfunction "1_1") (pintype "passive"))
      (node (ref "C20") (pin "1") (pinfunction "1_1") (pintype "passive"))
      (node (ref "C21") (pin "1") (pinfunction "1_1") (pintype "passive"))
      (node (ref "C22") (pin "1") (pinfunction "1_1") (pintype "passive"))
      (node (ref "C23") (pin "1") (pinfunction "1_1") (pintype "passive"))
      (node (ref "C3") (pin "2") (pinfunction "2_2") (pintype "passive"))
      (node (ref "C7") (pin "1") (pinfunction "1_1") (pintype "passive"))
      (node (ref "J4") (pin "1") (pinfunction "1_1") (pintype "passive"))
      (node (ref "J7") (pin "1") (pinfunction "VCC_1") (pintype "passive"))
      (node (ref "J8") (pin "1") (pinfunction "0_1") (pintype "passive"))
      (node (ref "P2") (pin "4") (pinfunction "4_4") (pintype "passive"))
      (node (ref "U1") (pin "1") (pinfunction "VDD_1") (pintype "passive"))
      (node (ref "U10") (pin "10") (pinfunction "~{SRCLR}_10") (pintype "input"))
      (node (ref "U10") (pin "16") (pinfunction "VCC_16") (pintype "power_in"))
      (node (ref "U11") (pin "10") (pinfunction "~{SRCLR}_10") (pintype "input"))
      (node (ref "U11") (pin "16") (pinfunction "VCC_16") (pintype "power_in"))
      (node (ref "U12") (pin "10") (pinfunction "~{SRCLR}_10") (pintype "input"))
      (node (ref "U12") (pin "16") (pinfunction "VCC_16") (pintype "power_in"))
      (node (ref "U2") (pin "1") (pinfunction "VDD_1") (pintype "passive"))
      (node (ref "U3") (pin "1") (pinfunction "VDD_1") (pintype "passive"))
      (node (ref "U4") (pin "1") (pinfunction "VDD_1") (pintype "passive"))
      (node (ref "U8") (pin "10") (pinfunction "~{SRCLR}_10") (pintype "input"))
      (node (ref "U8") (pin "16") (pinfunction "VCC_16") (pintype "power_in"))
      (node (ref "U9") (pin "10") (pinfunction "~{SRCLR}_10") (pintype "input"))
      (node (ref "U9") (pin "16") (pinfunction "VCC_16") (pintype "power_in"))
      (node (ref "VR1") (pin "2") (pinfunction "Vout_2") (pintype "passive"))
      (node (ref "VR2") (pin "3") (pinfunction "Vin_3") (pintype "passive"))
    )
    (net (code "2") (name "+12") (class "Default")
      (node (ref "C1") (pin "1") (pinfunction "1_1") (pintype "passive"))
      (node (ref "C2") (pin "2") (pinfunction "2_2") (pintype "passive"))
      (node (ref "J1") (pin "1") (pinfunction "1_1") (pintype "power_in"))
      (node (ref "J3") (pin "1") (pinfunction "1_1") (pintype "passive"))
      (node (ref "Q2") (pin "3") (pinfunction "C_3") (pintype "passive"))
      (node (ref "VR1") (pin "3") (pinfunction "Vin_3") (pintype "passive"))
    )
    (net (code "3") (name "/595_DataIN") (class "Default")
      (node (ref "U8") (pin "14") (pinfunction "SER_14") (pintype "input"))
    )
    (net (code "4") (name "/595_LatchCLK") (class "Default")
      (node (ref "U10") (pin "12") (pinfunction "RCLK_12") (pintype "input"))
      (node (ref "U11") (pin "12") (pinfunction "RCLK_12") (pintype "input"))
      (node (ref "U12") (pin "12") (pinfunction "RCLK_12") (pintype "input"))
      (node (ref "U8") (pin "12") (pinfunction "RCLK_12") (pintype "input"))
      (node (ref "U9") (pin "12") (pinfunction "RCLK_12") (pintype "input"))
    )
    (net (code "5") (name "/595_OE#") (class "Default")
      (node (ref "U10") (pin "13") (pinfunction "~{OE}_13") (pintype "input"))
      (node (ref "U11") (pin "13") (pinfunction "~{OE}_13") (pintype "input"))
      (node (ref "U12") (pin "13") (pinfunction "~{OE}_13") (pintype "input"))
      (node (ref "U8") (pin "13") (pinfunction "~{OE}_13") (pintype "input"))
      (node (ref "U9") (pin "13") (pinfunction "~{OE}_13") (pintype "input"))
    )
    (net (code "6") (name "/595_ShiftCLK") (class "Default")
      (node (ref "U10") (pin "11") (pinfunction "SRCLK_11") (pintype "input"))
      (node (ref "U11") (pin "11") (pinfunction "SRCLK_11") (pintype "input"))
      (node (ref "U12") (pin "11") (pinfunction "SRCLK_11") (pintype "input"))
      (node (ref "U8") (pin "11") (pinfunction "SRCLK_11") (pintype "input"))
      (node (ref "U9") (pin "11") (pinfunction "SRCLK_11") (pintype "input"))
    )
    (net (code "7") (name "/Atmosphere Lamp") (class "Default")
      (node (ref "P1") (pin "1") (pinfunction "1_1") (pintype "passive"))
      (node (ref "U6") (pin "23") (pinfunction "PA7_23") (pintype "bidirectional"))
    )
    (net (code "8") (name "/BEEP") (class "Default")
      (node (ref "R26") (pin "1") (pinfunction "1_1") (pintype "passive"))
      (node (ref "U6") (pin "15") (pinfunction "PA1_15") (pintype "bidirectional"))
    )
    (net (code "9") (name "/BT0") (class "Default")
      (node (ref "R16") (pin "2") (pinfunction "2_2") (pintype "passive"))
      (node (ref "R21") (pin "1") (pinfunction "1_1") (pintype "passive"))
      (node (ref "U6") (pin "60") (pinfunction "BOOT0_60") (pintype "input"))
    )
    (net (code "10") (name "/BT1") (class "Default")
      (node (ref "R13") (pin "2") (pinfunction "2_2") (pintype "passive"))
      (node (ref "U6") (pin "28") (pinfunction "PB2_28") (pintype "bidirectional"))
    )
    (net (code "11") (name "/BoostONOFF") (class "Default")
      (node (ref "Q2") (pin "1") (pinfunction "B_1") (pintype "passive"))
      (node (ref "U6") (pin "62") (pinfunction "PB9_62") (pintype "bidirectional"))
    )
    (net (code "12") (name "/DQ") (class "Default")
      (node (ref "R22") (pin "2") (pinfunction "2_2") (pintype "passive"))
      (node (ref "U13") (pin "2") (pinfunction "DQ_2") (pintype "passive"))
      (node (ref "U6") (pin "61") (pinfunction "PB8_61") (pintype "bidirectional"))
    )
    (net (code "13") (name "/Dot1") (class "Default")
      (node (ref "R3") (pin "1") (pinfunction "1_1") (pintype "passive"))
      (node (ref "U6") (pin "39") (pinfunction "PC8_39") (pintype "bidirectional"))
    )
    (net (code "14") (name "/Dot2") (class "Default")
      (node (ref "R9") (pin "2") (pinfunction "2_2") (pintype "passive"))
      (node (ref "U6") (pin "40") (pinfunction "PC9_40") (pintype "bidirectional"))
    )
    (net (code "15") (name "/Dot3") (class "Default")
      (node (ref "U6") (pin "51") (pinfunction "PC10_51") (pintype "bidirectional"))
    )
    (net (code "16") (name "/Dot4") (class "Default")
      (node (ref "U6") (pin "52") (pinfunction "PC11_52") (pintype "bidirectional"))
    )
    (net (code "17") (name "/HV_CLK") (class "Default")
      (node (ref "U6") (pin "25") (pinfunction "PC5_25") (pintype "bidirectional"))
    )
    (net (code "18") (name "/HV_DIN1") (class "Default")
      (node (ref "U6") (pin "8") (pinfunction "PC0_8") (pintype "bidirectional"))
    )
    (net (code "19") (name "/HV_DIN2") (class "Default")
      (node (ref "U6") (pin "9") (pinfunction "PC1_9") (pintype "bidirectional"))
    )
    (net (code "20") (name "/HV_DIN3") (class "Default")
      (node (ref "U6") (pin "10") (pinfunction "PC2_10") (pintype "bidirectional"))
    )
    (net (code "21") (name "/HV_DIN4") (class "Default")
      (node (ref "U6") (pin "11") (pinfunction "PC3_11") (pintype "bidirectional"))
    )
    (net (code "22") (name "/HV_LE") (class "Default")
      (node (ref "U6") (pin "24") (pinfunction "PC4_24") (pintype "bidirectional"))
    )
    (net (code "23") (name "/HV_POL") (class "Default")
      (node (ref "U6") (pin "37") (pinfunction "PC6_37") (pintype "bidirectional"))
    )
    (net (code "24") (name "/HX1838") (class "Default")
      (node (ref "R27") (pin "1") (pinfunction "1_1") (pintype "passive"))
      (node (ref "U15") (pin "1") (pinfunction "OUT_1") (pintype "passive"))
      (node (ref "U6") (pin "16") (pinfunction "PA2_16") (pintype "bidirectional"))
    )
    (net (code "25") (name "/INT#{slash}SQW") (class "Default")
      (node (ref "R25") (pin "1") (pinfunction "1_1") (pintype "passive"))
      (node (ref "U14") (pin "3") (pinfunction "~{INT}/SQW_3") (pintype "passive"))
    )
    (net (code "26") (name "/KEY_DEBUG") (class "Default")
      (node (ref "C5") (pin "2") (pinfunction "2_2") (pintype "passive"))
      (node (ref "R1") (pin "2") (pinfunction "2_2") (pintype "passive"))
      (node (ref "S1") (pin "2") (pinfunction "2_2") (pintype "passive"))
      (node (ref "U6") (pin "58") (pinfunction "PB6_58") (pintype "bidirectional"))
    )
    (net (code "27") (name "/LED_DEBUG") (class "Default")
      (node (ref "R12") (pin "2") (pinfunction "2_2") (pintype "passive"))
      (node (ref "U6") (pin "22") (pinfunction "PA6_22") (pintype "bidirectional"))
    )
    (net (code "28") (name "/MetalKey") (class "Default")
      (node (ref "C6") (pin "2") (pinfunction "2_2") (pintype "passive"))
      (node (ref "P1") (pin "4") (pinfunction "4_4") (pintype "passive"))
      (node (ref "R2") (pin "2") (pinfunction "2_2") (pintype "passive"))
      (node (ref "U6") (pin "36") (pinfunction "PB15_36") (pintype "bidirectional"))
    )
    (net (code "29") (name "/RGB") (class "Default")
      (node (ref "U1") (pin "4") (pinfunction "DI_4") (pintype "passive"))
      (node (ref "U6") (pin "56") (pinfunction "PB4_56") (pintype "bidirectional"))
    )
    (net (code "30") (name "/RST") (class "Default")
      (node (ref "C18") (pin "2") (pinfunction "2_2") (pintype "passive"))
      (node (ref "D3") (pin "1") (pinfunction "A_1") (pintype "passive"))
      (node (ref "R17") (pin "2") (pinfunction "2_2") (pintype "passive"))
      (node (ref "S2") (pin "1") (pinfunction "1_1") (pintype "passive"))
      (node (ref "U6") (pin "7") (pinfunction "NRST_7") (pintype "bidirectional"))
    )
    (net (code "31") (name "/RX1") (class "Default")
      (node (ref "P3") (pin "2") (pinfunction "2_2") (pintype "passive"))
      (node (ref "U6") (pin "43") (pinfunction "PA10_43") (pintype "bidirectional"))
      (node (ref "U7") (pin "2") (pinfunction "TXD_2") (pintype "passive"))
    )
    (net (code "32") (name "/SCL") (class "Default")
      (node (ref "R23") (pin "2") (pinfunction "2_2") (pintype "passive"))
      (node (ref "U14") (pin "16") (pinfunction "SCL_16") (pintype "passive"))
      (node (ref "U6") (pin "27") (pinfunction "PB1_27") (pintype "bidirectional"))
    )
    (net (code "33") (name "/SDA") (class "Default")
      (node (ref "R24") (pin "2") (pinfunction "2_2") (pintype "passive"))
      (node (ref "U14") (pin "15") (pinfunction "SDA_15") (pintype "passive"))
      (node (ref "U6") (pin "26") (pinfunction "PB0_26") (pintype "bidirectional"))
    )
    (net (code "34") (name "/SWCLK") (class "Default")
      (node (ref "P2") (pin "2") (pinfunction "2_2") (pintype "passive"))
      (node (ref "U6") (pin "49") (pinfunction "PA14_49") (pintype "bidirectional"))
    )
    (net (code "35") (name "/SWDIO") (class "Default")
      (node (ref "P2") (pin "3") (pinfunction "3_3") (pintype "passive"))
      (node (ref "U6") (pin "46") (pinfunction "PA13_46") (pintype "bidirectional"))
    )
    (net (code "36") (name "/TX1") (class "Default")
      (node (ref "P3") (pin "1") (pinfunction "1_1") (pintype "passive"))
      (node (ref "U6") (pin "42") (pinfunction "PA9_42") (pintype "bidirectional"))
      (node (ref "U7") (pin "3") (pinfunction "RXD_3") (pintype "passive"))
    )
    (net (code "37") (name "/Tube1-0") (class "Default")
      (node (ref "Q5") (pin "1") (pinfunction "B_1") (pintype "passive"))
      (node (ref "U9") (pin "1") (pinfunction "QB_1") (pintype "tri_state"))
    )
    (net (code "38") (name "/Tube1-1") (class "Default")
      (node (ref "Q14") (pin "1") (pinfunction "B_1") (pintype "passive"))
      (node (ref "U9") (pin "15") (pinfunction "QA_15") (pintype "tri_state"))
    )
    (net (code "39") (name "/Tube1-2") (class "Default")
      (node (ref "Q13") (pin "1") (pinfunction "B_1") (pintype "passive"))
      (node (ref "U8") (pin "7") (pinfunction "QH_7") (pintype "tri_state"))
    )
    (net (code "40") (name "/Tube1-3") (class "Default")
      (node (ref "Q12") (pin "1") (pinfunction "B_1") (pintype "passive"))
      (node (ref "U8") (pin "6") (pinfunction "QG_6") (pintype "tri_state"))
    )
    (net (code "41") (name "/Tube1-4") (class "Default")
      (node (ref "Q11") (pin "1") (pinfunction "B_1") (pintype "passive"))
      (node (ref "U8") (pin "5") (pinfunction "QF_5") (pintype "tri_state"))
    )
    (net (code "42") (name "/Tube1-5") (class "Default")
      (node (ref "Q10") (pin "1") (pinfunction "B_1") (pintype "passive"))
      (node (ref "U8") (pin "4") (pinfunction "QE_4") (pintype "tri_state"))
    )
    (net (code "43") (name "/Tube1-6") (class "Default")
      (node (ref "Q9") (pin "1") (pinfunction "B_1") (pintype "passive"))
      (node (ref "U8") (pin "3") (pinfunction "QD_3") (pintype "tri_state"))
    )
    (net (code "44") (name "/Tube1-7") (class "Default")
      (node (ref "Q8") (pin "1") (pinfunction "B_1") (pintype "passive"))
      (node (ref "U8") (pin "2") (pinfunction "QC_2") (pintype "tri_state"))
    )
    (net (code "45") (name "/Tube1-8") (class "Default")
      (node (ref "Q7") (pin "1") (pinfunction "B_1") (pintype "passive"))
      (node (ref "U8") (pin "1") (pinfunction "QB_1") (pintype "tri_state"))
    )
    (net (code "46") (name "/Tube1-9") (class "Default")
      (node (ref "Q6") (pin "1") (pinfunction "B_1") (pintype "passive"))
      (node (ref "U8") (pin "15") (pinfunction "QA_15") (pintype "tri_state"))
    )
    (net (code "47") (name "/Tube2-0") (class "Default")
      (node (ref "Q15") (pin "1") (pinfunction "B_1") (pintype "passive"))
      (node (ref "U10") (pin "3") (pinfunction "QD_3") (pintype "tri_state"))
    )
    (net (code "48") (name "/Tube2-1") (class "Default")
      (node (ref "Q24") (pin "1") (pinfunction "B_1") (pintype "passive"))
      (node (ref "U10") (pin "2") (pinfunction "QC_2") (pintype "tri_state"))
    )
    (net (code "49") (name "/Tube2-2") (class "Default")
      (node (ref "Q23") (pin "1") (pinfunction "B_1") (pintype "passive"))
      (node (ref "U10") (pin "1") (pinfunction "QB_1") (pintype "tri_state"))
    )
    (net (code "50") (name "/Tube2-3") (class "Default")
      (node (ref "Q22") (pin "1") (pinfunction "B_1") (pintype "passive"))
      (node (ref "U10") (pin "15") (pinfunction "QA_15") (pintype "tri_state"))
    )
    (net (code "51") (name "/Tube2-4") (class "Default")
      (node (ref "Q21") (pin "1") (pinfunction "B_1") (pintype "passive"))
      (node (ref "U9") (pin "7") (pinfunction "QH_7") (pintype "tri_state"))
    )
    (net (code "52") (name "/Tube2-5") (class "Default")
      (node (ref "Q20") (pin "1") (pinfunction "B_1") (pintype "passive"))
      (node (ref "U9") (pin "6") (pinfunction "QG_6") (pintype "tri_state"))
    )
    (net (code "53") (name "/Tube2-6") (class "Default")
      (node (ref "Q19") (pin "1") (pinfunction "B_1") (pintype "passive"))
      (node (ref "U9") (pin "5") (pinfunction "QF_5") (pintype "tri_state"))
    )
    (net (code "54") (name "/Tube2-7") (class "Default")
      (node (ref "Q18") (pin "1") (pinfunction "B_1") (pintype "passive"))
      (node (ref "U9") (pin "4") (pinfunction "QE_4") (pintype "tri_state"))
    )
    (net (code "55") (name "/Tube2-8") (class "Default")
      (node (ref "Q17") (pin "1") (pinfunction "B_1") (pintype "passive"))
      (node (ref "U9") (pin "3") (pinfunction "QD_3") (pintype "tri_state"))
    )
    (net (code "56") (name "/Tube2-9") (class "Default")
      (node (ref "Q16") (pin "1") (pinfunction "B_1") (pintype "passive"))
      (node (ref "U9") (pin "2") (pinfunction "QC_2") (pintype "tri_state"))
    )
    (net (code "57") (name "/Tube3-0") (class "Default")
      (node (ref "Q25") (pin "1") (pinfunction "B_1") (pintype "passive"))
      (node (ref "U11") (pin "5") (pinfunction "QF_5") (pintype "tri_state"))
    )
    (net (code "58") (name "/Tube3-1") (class "Default")
      (node (ref "U11") (pin "4") (pinfunction "QE_4") (pintype "tri_state"))
    )
    (net (code "59") (name "/Tube3-2") (class "Default")
      (node (ref "Q33") (pin "1") (pinfunction "B_1") (pintype "passive"))
      (node (ref "U11") (pin "3") (pinfunction "QD_3") (pintype "tri_state"))
    )
    (net (code "60") (name "/Tube3-3") (class "Default")
      (node (ref "Q32") (pin "1") (pinfunction "B_1") (pintype "passive"))
      (node (ref "U11") (pin "2") (pinfunction "QC_2") (pintype "tri_state"))
    )
    (net (code "61") (name "/Tube3-4") (class "Default")
      (node (ref "Q31") (pin "1") (pinfunction "B_1") (pintype "passive"))
      (node (ref "U11") (pin "1") (pinfunction "QB_1") (pintype "tri_state"))
    )
    (net (code "62") (name "/Tube3-5") (class "Default")
      (node (ref "Q30") (pin "1") (pinfunction "B_1") (pintype "passive"))
      (node (ref "U11") (pin "15") (pinfunction "QA_15") (pintype "tri_state"))
    )
    (net (code "63") (name "/Tube3-6") (class "Default")
      (node (ref "Q29") (pin "1") (pinfunction "B_1") (pintype "passive"))
      (node (ref "U10") (pin "7") (pinfunction "QH_7") (pintype "tri_state"))
    )
    (net (code "64") (name "/Tube3-7") (class "Default")
      (node (ref "Q28") (pin "1") (pinfunction "B_1") (pintype "passive"))
      (node (ref "U10") (pin "6") (pinfunction "QG_6") (pintype "tri_state"))
    )
    (net (code "65") (name "/Tube3-8") (class "Default")
      (node (ref "Q27") (pin "1") (pinfunction "B_1") (pintype "passive"))
      (node (ref "U10") (pin "5") (pinfunction "QF_5") (pintype "tri_state"))
    )
    (net (code "66") (name "/Tube3-9") (class "Default")
      (node (ref "Q26") (pin "1") (pinfunction "B_1") (pintype "passive"))
      (node (ref "U10") (pin "4") (pinfunction "QE_4") (pintype "tri_state"))
    )
    (net (code "67") (name "/Tube4-0") (class "Default")
      (node (ref "Q35") (pin "1") (pinfunction "B_1") (pintype "passive"))
      (node (ref "U12") (pin "7") (pinfunction "QH_7") (pintype "tri_state"))
    )
    (net (code "68") (name "/Tube4-1") (class "Default")
      (node (ref "Q44") (pin "1") (pinfunction "B_1") (pintype "passive"))
      (node (ref "U12") (pin "6") (pinfunction "QG_6") (pintype "tri_state"))
    )
    (net (code "69") (name "/Tube4-2") (class "Default")
      (node (ref "Q43") (pin "1") (pinfunction "B_1") (pintype "passive"))
      (node (ref "U12") (pin "5") (pinfunction "QF_5") (pintype "tri_state"))
    )
    (net (code "70") (name "/Tube4-3") (class "Default")
      (node (ref "U12") (pin "4") (pinfunction "QE_4") (pintype "tri_state"))
    )
    (net (code "71") (name "/Tube4-4") (class "Default")
      (node (ref "Q41") (pin "1") (pinfunction "B_1") (pintype "passive"))
      (node (ref "U12") (pin "3") (pinfunction "QD_3") (pintype "tri_state"))
    )
    (net (code "72") (name "/Tube4-5") (class "Default")
      (node (ref "Q40") (pin "1") (pinfunction "B_1") (pintype "passive"))
      (node (ref "U12") (pin "2") (pinfunction "QC_2") (pintype "tri_state"))
    )
    (net (code "73") (name "/Tube4-6") (class "Default")
      (node (ref "Q39") (pin "1") (pinfunction "B_1") (pintype "passive"))
      (node (ref "U12") (pin "1") (pinfunction "QB_1") (pintype "tri_state"))
    )
    (net (code "74") (name "/Tube4-7") (class "Default")
      (node (ref "Q38") (pin "1") (pinfunction "B_1") (pintype "passive"))
      (node (ref "U12") (pin "15") (pinfunction "QA_15") (pintype "tri_state"))
    )
    (net (code "75") (name "/Tube4-8") (class "Default")
      (node (ref "Q37") (pin "1") (pinfunction "B_1") (pintype "passive"))
      (node (ref "U11") (pin "7") (pinfunction "QH_7") (pintype "tri_state"))
    )
    (net (code "76") (name "/Tube4-9") (class "Default")
      (node (ref "Q36") (pin "1") (pinfunction "B_1") (pintype "passive"))
      (node (ref "U11") (pin "6") (pinfunction "QG_6") (pintype "tri_state"))
    )
    (net (code "77") (name "/UD+") (class "Default")
      (node (ref "J7") (pin "3") (pinfunction "D+_3") (pintype "passive"))
      (node (ref "U7") (pin "5") (pinfunction "UD+_5") (pintype "passive"))
    )
    (net (code "78") (name "/UD-") (class "Default")
      (node (ref "J7") (pin "2") (pinfunction "D-_2") (pintype "passive"))
      (node (ref "U7") (pin "6") (pinfunction "UD-_6") (pintype "passive"))
    )
    (net (code "79") (name "3V3") (class "Default")
      (node (ref "C15") (pin "1") (pinfunction "1_1") (pintype "passive"))
      (node (ref "C16") (pin "1") (pinfunction "1_1") (pintype "passive"))
      (node (ref "C17") (pin "1") (pinfunction "1_1") (pintype "passive"))
      (node (ref "C27") (pin "1") (pinfunction "1_1") (pintype "passive"))
      (node (ref "C4") (pin "2") (pinfunction "2_2") (pintype "passive"))
      (node (ref "D2") (pin "A") (pinfunction "A_A") (pintype "passive"))
      (node (ref "J5") (pin "1") (pinfunction "1_1") (pintype "passive"))
      (node (ref "P1") (pin "2") (pinfunction "2_2") (pintype "passive"))
      (node (ref "Q46") (pin "2") (pinfunction "E_2") (pintype "passive"))
      (node (ref "R1") (pin "1") (pinfunction "1_1") (pintype "passive"))
      (node (ref "R17") (pin "1") (pinfunction "1_1") (pintype "passive"))
      (node (ref "R18") (pin "2") (pinfunction "2_2") (pintype "passive"))
      (node (ref "R2") (pin "1") (pinfunction "1_1") (pintype "passive"))
      (node (ref "R22") (pin "1") (pinfunction "1_1") (pintype "passive"))
      (node (ref "R23") (pin "1") (pinfunction "1_1") (pintype "passive"))
      (node (ref "R24") (pin "1") (pinfunction "1_1") (pintype "passive"))
      (node (ref "R25") (pin "2") (pinfunction "2_2") (pintype "passive"))
      (node (ref "R27") (pin "2") (pinfunction "2_2") (pintype "passive"))
      (node (ref "U13") (pin "3") (pinfunction "VDD_3") (pintype "passive"))
      (node (ref "U14") (pin "2") (pinfunction "VCC_2") (pintype "passive"))
      (node (ref "U15") (pin "3") (pinfunction "VCC_3") (pintype "passive"))
      (node (ref "U6") (pin "1") (pinfunction "VBAT_1") (pintype "power_in"))
      (node (ref "U6") (pin "13") (pinfunction "VDDA_13") (pintype "power_in"))
      (node (ref "U6") (pin "19") (pinfunction "VDD_4_19") (pintype "power_in"))
      (node (ref "U6") (pin "32") (pinfunction "VDD_1_32") (pintype "power_in"))
      (node (ref "U6") (pin "48") (pinfunction "VDD_2_48") (pintype "power_in"))
      (node (ref "U6") (pin "64") (pinfunction "VDD_3_64") (pintype "power_in"))
      (node (ref "U7") (pin "16") (pinfunction "VCC_16") (pintype "passive"))
      (node (ref "VR2") (pin "2") (pinfunction "Vout_2") (pintype "passive"))
    )
    (net (code "80") (name "DGND") (class "Default")
      (node (ref "BT1") (pin "2") (pinfunction "-_2") (pintype "passive"))
      (node (ref "C13") (pin "1") (pinfunction "1_1") (pintype "passive"))
      (node (ref "C14") (pin "1") (pinfunction "1_1") (pintype "passive"))
      (node (ref "C15") (pin "2") (pinfunction "2_2") (pintype "passive"))
      (node (ref "C16") (pin "2") (pinfunction "2_2") (pintype "passive"))
      (node (ref "C17") (pin "2") (pinfunction "2_2") (pintype "passive"))
      (node (ref "C18") (pin "1") (pinfunction "1_1") (pintype "passive"))
      (node (ref "C19") (pin "2") (pinfunction "2_2") (pintype "passive"))
      (node (ref "C20") (pin "2") (pinfunction "2_2") (pintype "passive"))
      (node (ref "C21") (pin "2") (pinfunction "2_2") (pintype "passive"))
      (node (ref "C22") (pin "2") (pinfunction "2_2") (pintype "passive"))
      (node (ref "C23") (pin "2") (pinfunction "2_2") (pintype "passive"))
      (node (ref "C24") (pin "2") (pinfunction "2_2") (pintype "passive"))
      (node (ref "C25") (pin "2") (pinfunction "2_2") (pintype "passive"))
      (node (ref "C26") (pin "2") (pinfunction "2_2") (pintype "passive"))
      (node (ref "C27") (pin "2") (pinfunction "2_2") (pintype "passive"))
      (node (ref "C5") (pin "1") (pinfunction "1_1") (pintype "passive"))
      (node (ref "C6") (pin "1") (pinfunction "1_1") (pintype "passive"))
      (node (ref "J7") (pin "4") (pinfunction "ID_4") (pintype "passive"))
      (node (ref "J7") (pin "5") (pinfunction "VSS_5") (pintype "passive"))
      (node (ref "L2") (pin "2") (pinfunction "2_2") (pintype "passive"))
      (node (ref "P1") (pin "3") (pinfunction "3_3") (pintype "passive"))
      (node (ref "P2") (pin "1") (pinfunction "1_1") (pintype "passive"))
      (node (ref "Q47") (pin "2") (pinfunction "E_2") (pintype "passive"))
      (node (ref "R13") (pin "1") (pinfunction "1_1") (pintype "passive"))
      (node (ref "R16") (pin "1") (pinfunction "1_1") (pintype "passive"))
      (node (ref "S1") (pin "1") (pinfunction "1_1") (pintype "passive"))
      (node (ref "S2") (pin "2") (pinfunction "2_2") (pintype "passive"))
      (node (ref "U10") (pin "8") (pinfunction "GND_8") (pintype "power_in"))
      (node (ref "U11") (pin "8") (pinfunction "GND_8") (pintype "power_in"))
      (node (ref "U12") (pin "8") (pinfunction "GND_8") (pintype "power_in"))
      (node (ref "U13") (pin "1") (pinfunction "GND_1") (pintype "passive"))
      (node (ref "U14") (pin "10") (pinfunction "N.C._10") (pintype "passive"))
      (node (ref "U14") (pin "11") (pinfunction "N.C._11") (pintype "passive"))
      (node (ref "U14") (pin "12") (pinfunction "N.C._12") (pintype "passive"))
      (node (ref "U14") (pin "13") (pinfunction "GND_13") (pintype "passive"))
      (node (ref "U14") (pin "5") (pinfunction "N.C._5") (pintype "passive"))
      (node (ref "U14") (pin "6") (pinfunction "N.C._6") (pintype "passive"))
      (node (ref "U14") (pin "7") (pinfunction "N.C._7") (pintype "passive"))
      (node (ref "U14") (pin "8") (pinfunction "N.C._8") (pintype "passive"))
      (node (ref "U14") (pin "9") (pinfunction "N.C._9") (pintype "passive"))
      (node (ref "U15") (pin "2") (pinfunction "GND_2") (pintype "passive"))
      (node (ref "U6") (pin "12") (pinfunction "VSSA_12") (pintype "power_in"))
      (node (ref "U6") (pin "18") (pinfunction "VSS_4_18") (pintype "power_in"))
      (node (ref "U6") (pin "31") (pinfunction "VSS_1_31") (pintype "power_in"))
      (node (ref "U6") (pin "47") (pinfunction "VSS_2_47") (pintype "power_in"))
      (node (ref "U6") (pin "63") (pinfunction "VSS_3_63") (pintype "power_in"))
      (node (ref "U7") (pin "1") (pinfunction "GND_1") (pintype "passive"))
      (node (ref "U8") (pin "8") (pinfunction "GND_8") (pintype "power_in"))
      (node (ref "U9") (pin "8") (pinfunction "GND_8") (pintype "power_in"))
    )
    (net (code "81") (name "GND") (class "Default")
      (node (ref "C1") (pin "2") (pinfunction "2_2") (pintype "passive"))
      (node (ref "C10") (pin "2") (pinfunction "2_2") (pintype "passive"))
      (node (ref "C11") (pin "1") (pinfunction "1_1") (pintype "passive"))
      (node (ref "C12") (pin "2") (pinfunction "2_2") (pintype "passive"))
      (node (ref "C2") (pin "1") (pinfunction "1_1") (pintype "passive"))
      (node (ref "C3") (pin "1") (pinfunction "1_1") (pintype "passive"))
      (node (ref "C4") (pin "1") (pinfunction "1_1") (pintype "passive"))
      (node (ref "C7") (pin "2") (pinfunction "2_2") (pintype "passive"))
      (node (ref "C8") (pin "1") (pinfunction "1_1") (pintype "passive"))
      (node (ref "C9") (pin "2") (pinfunction "2_2") (pintype "passive"))
      (node (ref "J1") (pin "2") (pinfunction "2_2") (pintype "power_in"))
      (node (ref "J1") (pin "3") (pinfunction "3_3") (pintype "power_in"))
      (node (ref "J6") (pin "1") (pinfunction "1_1") (pintype "passive"))
      (node (ref "L2") (pin "1") (pinfunction "1_1") (pintype "passive"))
      (node (ref "Q1") (pin "2") (pinfunction "E_2") (pintype "passive"))
      (node (ref "Q10") (pin "2") (pinfunction "E_2") (pintype "passive"))
      (node (ref "Q11") (pin "2") (pinfunction "E_2") (pintype "passive"))
      (node (ref "Q12") (pin "2") (pinfunction "E_2") (pintype "passive"))
      (node (ref "Q13") (pin "2") (pinfunction "E_2") (pintype "passive"))
      (node (ref "Q14") (pin "2") (pinfunction "E_2") (pintype "passive"))
      (node (ref "Q15") (pin "2") (pinfunction "E_2") (pintype "passive"))
      (node (ref "Q16") (pin "2") (pinfunction "E_2") (pintype "passive"))
      (node (ref "Q17") (pin "2") (pinfunction "E_2") (pintype "passive"))
      (node (ref "Q18") (pin "2") (pinfunction "E_2") (pintype "passive"))
      (node (ref "Q19") (pin "2") (pinfunction "E_2") (pintype "passive"))
      (node (ref "Q20") (pin "2") (pinfunction "E_2") (pintype "passive"))
      (node (ref "Q21") (pin "2") (pinfunction "E_2") (pintype "passive"))
      (node (ref "Q22") (pin "2") (pinfunction "E_2") (pintype "passive"))
      (node (ref "Q23") (pin "2") (pinfunction "E_2") (pintype "passive"))
      (node (ref "Q24") (pin "2") (pinfunction "E_2") (pintype "passive"))
      (node (ref "Q25") (pin "2") (pinfunction "E_2") (pintype "passive"))
      (node (ref "Q26") (pin "2") (pinfunction "E_2") (pintype "passive"))
      (node (ref "Q27") (pin "2") (pinfunction "E_2") (pintype "passive"))
      (node (ref "Q28") (pin "2") (pinfunction "E_2") (pintype "passive"))
      (node (ref "Q29") (pin "2") (pinfunction "E_2") (pintype "passive"))
      (node (ref "Q3") (pin "2") (pinfunction "E_2") (pintype "passive"))
      (node (ref "Q30") (pin "2") (pinfunction "E_2") (pintype "passive"))
      (node (ref "Q31") (pin "2") (pinfunction "E_2") (pintype "passive"))
      (node (ref "Q32") (pin "2") (pinfunction "E_2") (pintype "passive"))
      (node (ref "Q33") (pin "2") (pinfunction "E_2") (pintype "passive"))
      (node (ref "Q34") (pin "2") (pinfunction "E_2") (pintype "passive"))
      (node (ref "Q35") (pin "2") (pinfunction "E_2") (pintype "passive"))
      (node (ref "Q36") (pin "2") (pinfunction "E_2") (pintype "passive"))
      (node (ref "Q37") (pin "2") (pinfunction "E_2") (pintype "passive"))
      (node (ref "Q38") (pin "2") (pinfunction "E_2") (pintype "passive"))
      (node (ref "Q39") (pin "2") (pinfunction "E_2") (pintype "passive"))
      (node (ref "Q4") (pin "3") (pinfunction "S_3") (pintype "passive"))
      (node (ref "Q40") (pin "2") (pinfunction "E_2") (pintype "passive"))
      (node (ref "Q41") (pin "2") (pinfunction "E_2") (pintype "passive"))
      (node (ref "Q42") (pin "2") (pinfunction "E_2") (pintype "passive"))
      (node (ref "Q43") (pin "2") (pinfunction "E_2") (pintype "passive"))
      (node (ref "Q44") (pin "2") (pinfunction "E_2") (pintype "passive"))
      (node (ref "Q5") (pin "2") (pinfunction "E_2") (pintype "passive"))
      (node (ref "Q6") (pin "2") (pinfunction "E_2") (pintype "passive"))
      (node (ref "Q7") (pin "2") (pinfunction "E_2") (pintype "passive"))
      (node (ref "Q8") (pin "2") (pinfunction "E_2") (pintype "passive"))
      (node (ref "Q9") (pin "2") (pinfunction "E_2") (pintype "passive"))
      (node (ref "R10") (pin "1") (pinfunction "1_1") (pintype "passive"))
      (node (ref "R4") (pin "1") (pinfunction "1_1") (pintype "passive"))
      (node (ref "U1") (pin "3") (pinfunction "VSS_3") (pintype "passive"))
      (node (ref "U2") (pin "3") (pinfunction "VSS_3") (pintype "passive"))
      (node (ref "U3") (pin "3") (pinfunction "VSS_3") (pintype "passive"))
      (node (ref "U4") (pin "3") (pinfunction "VSS_3") (pintype "passive"))
      (node (ref "U5") (pin "4") (pinfunction "GND_4") (pintype "passive"))
      (node (ref "VR1") (pin "1") (pinfunction "GND_1") (pintype "passive"))
      (node (ref "VR2") (pin "1") (pinfunction "GND_1") (pintype "passive"))
    )
    (net (code "82") (name "Net-(*1-Anode)") (class "Default")
      (node (ref "*1") (pin "2") (pinfunction "Anode_2") (pintype "passive"))
      (node (ref "R7") (pin "1") (pinfunction "1_1") (pintype "passive"))
    )
    (net (code "83") (name "Net-(*1-K'0')") (class "Default")
      (node (ref "*1") (pin "3") (pinfunction "K'0'_3") (pintype "passive"))
      (node (ref "Q15") (pin "3") (pinfunction "C_3") (pintype "passive"))
    )
    (net (code "84") (name "Net-(*1-K'1')") (class "Default")
      (node (ref "*1") (pin "13") (pinfunction "K'1'_13") (pintype "passive"))
      (node (ref "Q24") (pin "3") (pinfunction "C_3") (pintype "passive"))
    )
    (net (code "85") (name "Net-(*1-K'2')") (class "Default")
      (node (ref "*1") (pin "12") (pinfunction "K'2'_12") (pintype "passive"))
      (node (ref "Q23") (pin "3") (pinfunction "C_3") (pintype "passive"))
    )
    (net (code "86") (name "Net-(*1-K'3')") (class "Default")
      (node (ref "*1") (pin "11") (pinfunction "K'3'_11") (pintype "passive"))
      (node (ref "Q22") (pin "3") (pinfunction "C_3") (pintype "passive"))
    )
    (net (code "87") (name "Net-(*1-K'4')") (class "Default")
      (node (ref "*1") (pin "10") (pinfunction "K'4'_10") (pintype "passive"))
      (node (ref "Q21") (pin "3") (pinfunction "C_3") (pintype "passive"))
    )
    (net (code "88") (name "Net-(*1-K'5')") (class "Default")
      (node (ref "*1") (pin "9") (pinfunction "K'5'_9") (pintype "passive"))
      (node (ref "Q20") (pin "3") (pinfunction "C_3") (pintype "passive"))
    )
    (net (code "89") (name "Net-(*1-K'6')") (class "Default")
      (node (ref "*1") (pin "7") (pinfunction "K'6'_7") (pintype "passive"))
      (node (ref "Q19") (pin "3") (pinfunction "C_3") (pintype "passive"))
    )
    (net (code "90") (name "Net-(*1-K'7')") (class "Default")
      (node (ref "*1") (pin "6") (pinfunction "K'7'_6") (pintype "passive"))
      (node (ref "Q18") (pin "3") (pinfunction "C_3") (pintype "passive"))
    )
    (net (code "91") (name "Net-(*1-K'8')") (class "Default")
      (node (ref "*1") (pin "5") (pinfunction "K'8'_5") (pintype "passive"))
      (node (ref "Q17") (pin "3") (pinfunction "C_3") (pintype "passive"))
    )
    (net (code "92") (name "Net-(*1-K'9')") (class "Default")
      (node (ref "*1") (pin "4") (pinfunction "K'9'_4") (pintype "passive"))
      (node (ref "Q16") (pin "3") (pinfunction "C_3") (pintype "passive"))
    )
    (net (code "93") (name "Net-(*2-Anode)") (class "Default")
      (node (ref "*2") (pin "2") (pinfunction "Anode_2") (pintype "passive"))
      (node (ref "R8") (pin "1") (pinfunction "1_1") (pintype "passive"))
    )
    (net (code "94") (name "Net-(*2-K'0')") (class "Default")
      (node (ref "*2") (pin "3") (pinfunction "K'0'_3") (pintype "passive"))
      (node (ref "Q5") (pin "3") (pinfunction "C_3") (pintype "passive"))
    )
    (net (code "95") (name "Net-(*2-K'1')") (class "Default")
      (node (ref "*2") (pin "13") (pinfunction "K'1'_13") (pintype "passive"))
      (node (ref "Q14") (pin "3") (pinfunction "C_3") (pintype "passive"))
    )
    (net (code "96") (name "Net-(*2-K'2')") (class "Default")
      (node (ref "*2") (pin "12") (pinfunction "K'2'_12") (pintype "passive"))
      (node (ref "Q13") (pin "3") (pinfunction "C_3") (pintype "passive"))
    )
    (net (code "97") (name "Net-(*2-K'3')") (class "Default")
      (node (ref "*2") (pin "11") (pinfunction "K'3'_11") (pintype "passive"))
      (node (ref "Q12") (pin "3") (pinfunction "C_3") (pintype "passive"))
    )
    (net (code "98") (name "Net-(*2-K'4')") (class "Default")
      (node (ref "*2") (pin "10") (pinfunction "K'4'_10") (pintype "passive"))
      (node (ref "Q11") (pin "3") (pinfunction "C_3") (pintype "passive"))
    )
    (net (code "99") (name "Net-(*2-K'5')") (class "Default")
      (node (ref "*2") (pin "9") (pinfunction "K'5'_9") (pintype "passive"))
      (node (ref "Q10") (pin "3") (pinfunction "C_3") (pintype "passive"))
    )
    (net (code "100") (name "Net-(*2-K'6')") (class "Default")
      (node (ref "*2") (pin "7") (pinfunction "K'6'_7") (pintype "passive"))
      (node (ref "Q9") (pin "3") (pinfunction "C_3") (pintype "passive"))
    )
    (net (code "101") (name "Net-(*2-K'7')") (class "Default")
      (node (ref "*2") (pin "6") (pinfunction "K'7'_6") (pintype "passive"))
      (node (ref "Q8") (pin "3") (pinfunction "C_3") (pintype "passive"))
    )
    (net (code "102") (name "Net-(*2-K'8')") (class "Default")
      (node (ref "*2") (pin "5") (pinfunction "K'8'_5") (pintype "passive"))
      (node (ref "Q7") (pin "3") (pinfunction "C_3") (pintype "passive"))
    )
    (net (code "103") (name "Net-(*2-K'9')") (class "Default")
      (node (ref "*2") (pin "4") (pinfunction "K'9'_4") (pintype "passive"))
      (node (ref "Q6") (pin "3") (pinfunction "C_3") (pintype "passive"))
    )
    (net (code "104") (name "Net-(*3-Anode)") (class "Default")
      (node (ref "*3") (pin "2") (pinfunction "Anode_2") (pintype "passive"))
      (node (ref "R14") (pin "1") (pinfunction "1_1") (pintype "passive"))
    )
    (net (code "105") (name "Net-(*3-K'0')") (class "Default")
      (node (ref "*3") (pin "3") (pinfunction "K'0'_3") (pintype "passive"))
      (node (ref "Q35") (pin "3") (pinfunction "C_3") (pintype "passive"))
    )
    (net (code "106") (name "Net-(*3-K'1')") (class "Default")
      (node (ref "*3") (pin "13") (pinfunction "K'1'_13") (pintype "passive"))
      (node (ref "Q44") (pin "3") (pinfunction "C_3") (pintype "passive"))
    )
    (net (code "107") (name "Net-(*3-K'2')") (class "Default")
      (node (ref "*3") (pin "12") (pinfunction "K'2'_12") (pintype "passive"))
      (node (ref "Q43") (pin "3") (pinfunction "C_3") (pintype "passive"))
    )
    (net (code "108") (name "Net-(*3-K'3')") (class "Default")
      (node (ref "*3") (pin "11") (pinfunction "K'3'_11") (pintype "passive"))
      (node (ref "Q42") (pin "3") (pinfunction "C_3") (pintype "passive"))
    )
    (net (code "109") (name "Net-(*3-K'4')") (class "Default")
      (node (ref "*3") (pin "10") (pinfunction "K'4'_10") (pintype "passive"))
      (node (ref "Q41") (pin "3") (pinfunction "C_3") (pintype "passive"))
    )
    (net (code "110") (name "Net-(*3-K'5')") (class "Default")
      (node (ref "*3") (pin "9") (pinfunction "K'5'_9") (pintype "passive"))
      (node (ref "Q40") (pin "3") (pinfunction "C_3") (pintype "passive"))
    )
    (net (code "111") (name "Net-(*3-K'6')") (class "Default")
      (node (ref "*3") (pin "7") (pinfunction "K'6'_7") (pintype "passive"))
      (node (ref "Q39") (pin "3") (pinfunction "C_3") (pintype "passive"))
    )
    (net (code "112") (name "Net-(*3-K'7')") (class "Default")
      (node (ref "*3") (pin "6") (pinfunction "K'7'_6") (pintype "passive"))
      (node (ref "Q38") (pin "3") (pinfunction "C_3") (pintype "passive"))
    )
    (net (code "113") (name "Net-(*3-K'8')") (class "Default")
      (node (ref "*3") (pin "5") (pinfunction "K'8'_5") (pintype "passive"))
      (node (ref "Q37") (pin "3") (pinfunction "C_3") (pintype "passive"))
    )
    (net (code "114") (name "Net-(*3-K'9')") (class "Default")
      (node (ref "*3") (pin "4") (pinfunction "K'9'_4") (pintype "passive"))
      (node (ref "Q36") (pin "3") (pinfunction "C_3") (pintype "passive"))
    )
    (net (code "115") (name "Net-(*4-Anode)") (class "Default")
      (node (ref "*4") (pin "2") (pinfunction "Anode_2") (pintype "passive"))
      (node (ref "R15") (pin "1") (pinfunction "1_1") (pintype "passive"))
    )
    (net (code "116") (name "Net-(*4-K'0')") (class "Default")
      (node (ref "*4") (pin "3") (pinfunction "K'0'_3") (pintype "passive"))
      (node (ref "Q25") (pin "3") (pinfunction "C_3") (pintype "passive"))
    )
    (net (code "117") (name "Net-(*4-K'1')") (class "Default")
      (node (ref "*4") (pin "13") (pinfunction "K'1'_13") (pintype "passive"))
      (node (ref "Q34") (pin "3") (pinfunction "C_3") (pintype "passive"))
    )
    (net (code "118") (name "Net-(*4-K'2')") (class "Default")
      (node (ref "*4") (pin "12") (pinfunction "K'2'_12") (pintype "passive"))
      (node (ref "Q33") (pin "3") (pinfunction "C_3") (pintype "passive"))
    )
    (net (code "119") (name "Net-(*4-K'3')") (class "Default")
      (node (ref "*4") (pin "11") (pinfunction "K'3'_11") (pintype "passive"))
      (node (ref "Q32") (pin "3") (pinfunction "C_3") (pintype "passive"))
    )
    (net (code "120") (name "Net-(*4-K'4')") (class "Default")
      (node (ref "*4") (pin "10") (pinfunction "K'4'_10") (pintype "passive"))
      (node (ref "Q31") (pin "3") (pinfunction "C_3") (pintype "passive"))
    )
    (net (code "121") (name "Net-(*4-K'5')") (class "Default")
      (node (ref "*4") (pin "9") (pinfunction "K'5'_9") (pintype "passive"))
      (node (ref "Q30") (pin "3") (pinfunction "C_3") (pintype "passive"))
    )
    (net (code "122") (name "Net-(*4-K'6')") (class "Default")
      (node (ref "*4") (pin "7") (pinfunction "K'6'_7") (pintype "passive"))
      (node (ref "Q29") (pin "3") (pinfunction "C_3") (pintype "passive"))
    )
    (net (code "123") (name "Net-(*4-K'7')") (class "Default")
      (node (ref "*4") (pin "6") (pinfunction "K'7'_6") (pintype "passive"))
      (node (ref "Q28") (pin "3") (pinfunction "C_3") (pintype "passive"))
    )
    (net (code "124") (name "Net-(*4-K'8')") (class "Default")
      (node (ref "*4") (pin "5") (pinfunction "K'8'_5") (pintype "passive"))
      (node (ref "Q27") (pin "3") (pinfunction "C_3") (pintype "passive"))
    )
    (net (code "125") (name "Net-(*4-K'9')") (class "Default")
      (node (ref "*4") (pin "4") (pinfunction "K'9'_4") (pintype "passive"))
      (node (ref "Q26") (pin "3") (pinfunction "C_3") (pintype "passive"))
    )
    (net (code "126") (name "Net-(BT1-+)") (class "Default")
      (node (ref "BT1") (pin "1") (pinfunction "+_1") (pintype "passive"))
      (node (ref "U14") (pin "14") (pinfunction "VBAT_14") (pintype "passive"))
    )
    (net (code "127") (name "Net-(D1-A)") (class "Default")
      (node (ref "D1") (pin "1") (pinfunction "A_1") (pintype "passive"))
      (node (ref "L1") (pin "2") (pinfunction "2_2") (pintype "passive"))
      (node (ref "Q4") (pin "2") (pinfunction "D_2") (pintype "passive"))
    )
    (net (code "128") (name "Net-(D2-PadK)") (class "Default")
      (node (ref "D2") (pin "K") (pinfunction "K_K") (pintype "passive"))
      (node (ref "R12") (pin "1") (pinfunction "1_1") (pintype "passive"))
    )
    (net (code "129") (name "Net-(D3-K)") (class "Default")
      (node (ref "D3") (pin "2") (pinfunction "K_2") (pintype "passive"))
      (node (ref "Q45") (pin "3") (pinfunction "C_3") (pintype "passive"))
      (node (ref "R18") (pin "1") (pinfunction "1_1") (pintype "passive"))
    )
    (net (code "130") (name "Net-(J8-1)") (class "Default")
      (node (ref "J8") (pin "2") (pinfunction "1_2") (pintype "passive"))
      (node (ref "Q47") (pin "3") (pinfunction "C_3") (pintype "passive"))
    )
    (net (code "131") (name "Net-(Q1-B)") (class "Default")
      (node (ref "Q1") (pin "1") (pinfunction "B_1") (pintype "passive"))
      (node (ref "R3") (pin "2") (pinfunction "2_2") (pintype "passive"))
    )
    (net (code "132") (name "Net-(Q1-C)") (class "Default")
      (node (ref "Q1") (pin "3") (pinfunction "C_3") (pintype "passive"))
      (node (ref "UP1") (pin "2") (pinfunction "2_2") (pintype "passive"))
    )
    (net (code "133") (name "Net-(Q2-E)") (class "Default")
      (node (ref "C11") (pin "2") (pinfunction "2_2") (pintype "passive"))
      (node (ref "C12") (pin "1") (pinfunction "1_1") (pintype "passive"))
      (node (ref "L1") (pin "1") (pinfunction "1_1") (pintype "passive"))
      (node (ref "Q2") (pin "2") (pinfunction "E_2") (pintype "passive"))
      (node (ref "U5") (pin "1") (pinfunction "SC_1") (pintype "passive"))
      (node (ref "U5") (pin "6") (pinfunction "VCC_6") (pintype "passive"))
      (node (ref "U5") (pin "7") (pinfunction "IPK_7") (pintype "passive"))
      (node (ref "U5") (pin "8") (pinfunction "DRI_8") (pintype "passive"))
    )
    (net (code "134") (name "Net-(Q3-B)") (class "Default")
      (node (ref "Q3") (pin "1") (pinfunction "B_1") (pintype "passive"))
      (node (ref "R9") (pin "1") (pinfunction "1_1") (pintype "passive"))
    )
    (net (code "135") (name "Net-(Q3-C)") (class "Default")
      (node (ref "Q3") (pin "3") (pinfunction "C_3") (pintype "passive"))
      (node (ref "UP2") (pin "2") (pinfunction "2_2") (pintype "passive"))
    )
    (net (code "136") (name "Net-(Q4-G)") (class "Default")
      (node (ref "Q4") (pin "1") (pinfunction "G_1") (pintype "passive"))
      (node (ref "R10") (pin "2") (pinfunction "2_2") (pintype "passive"))
      (node (ref "U5") (pin "2") (pinfunction "SE_2") (pintype "passive"))
    )
    (net (code "137") (name "Net-(Q45-B)") (class "Default")
      (node (ref "Q45") (pin "1") (pinfunction "B_1") (pintype "passive"))
      (node (ref "R19") (pin "2") (pinfunction "2_2") (pintype "passive"))
    )
    (net (code "138") (name "Net-(Q45-E)") (class "Default")
      (node (ref "Q45") (pin "2") (pinfunction "E_2") (pintype "passive"))
      (node (ref "R20") (pin "1") (pinfunction "1_1") (pintype "passive"))
      (node (ref "U7") (pin "11") (pinfunction "RTS#_11") (pintype "passive"))
    )
    (net (code "139") (name "Net-(Q46-B)") (class "Default")
      (node (ref "Q46") (pin "1") (pinfunction "B_1") (pintype "passive"))
      (node (ref "R20") (pin "2") (pinfunction "2_2") (pintype "passive"))
    )
    (net (code "140") (name "Net-(Q46-C)") (class "Default")
      (node (ref "Q46") (pin "3") (pinfunction "C_3") (pintype "passive"))
      (node (ref "R21") (pin "2") (pinfunction "2_2") (pintype "passive"))
    )
    (net (code "141") (name "Net-(Q47-B)") (class "Default")
      (node (ref "Q47") (pin "1") (pinfunction "B_1") (pintype "passive"))
      (node (ref "R26") (pin "2") (pinfunction "2_2") (pintype "passive"))
    )
    (net (code "142") (name "Net-(R6-Pad1)") (class "Default")
      (node (ref "R6") (pin "1") (pinfunction "1_1") (pintype "passive"))
      (node (ref "UP1") (pin "1") (pinfunction "1_1") (pintype "passive"))
    )
    (net (code "143") (name "Net-(R11-Pad1)") (class "Default")
      (node (ref "R11") (pin "1") (pinfunction "1_1") (pintype "passive"))
      (node (ref "UP2") (pin "1") (pinfunction "1_1") (pintype "passive"))
    )
    (net (code "144") (name "Net-(U1-DO)") (class "Default")
      (node (ref "U1") (pin "2") (pinfunction "DO_2") (pintype "passive"))
      (node (ref "U2") (pin "4") (pinfunction "DI_4") (pintype "passive"))
    )
    (net (code "145") (name "Net-(U2-DO)") (class "Default")
      (node (ref "U2") (pin "2") (pinfunction "DO_2") (pintype "passive"))
      (node (ref "U3") (pin "4") (pinfunction "DI_4") (pintype "passive"))
    )
    (net (code "146") (name "Net-(U3-DO)") (class "Default")
      (node (ref "U3") (pin "2") (pinfunction "DO_2") (pintype "passive"))
      (node (ref "U4") (pin "4") (pinfunction "DI_4") (pintype "passive"))
    )
    (net (code "147") (name "Net-(U5-FB)") (class "Default")
      (node (ref "C8") (pin "2") (pinfunction "2_2") (pintype "passive"))
      (node (ref "R4") (pin "2") (pinfunction "2_2") (pintype "passive"))
      (node (ref "R5") (pin "1") (pinfunction "1_1") (pintype "passive"))
      (node (ref "U5") (pin "5") (pinfunction "FB_5") (pintype "passive"))
    )
    (net (code "148") (name "Net-(U5-TC)") (class "Default")
      (node (ref "C9") (pin "1") (pinfunction "1_1") (pintype "passive"))
      (node (ref "U5") (pin "3") (pinfunction "TC_3") (pintype "passive"))
    )
    (net (code "149") (name "Net-(U6A-PD0-OSC_IN)") (class "Default")
      (node (ref "C13") (pin "2") (pinfunction "2_2") (pintype "passive"))
      (node (ref "U6") (pin "5") (pinfunction "PD0-OSC_IN_5") (pintype "bidirectional"))
      (node (ref "Y1") (pin "1") (pinfunction "OSC1_1") (pintype "passive"))
    )
    (net (code "150") (name "Net-(U6A-PD1)") (class "Default")
      (node (ref "C14") (pin "2") (pinfunction "2_2") (pintype "passive"))
      (node (ref "U6") (pin "6") (pinfunction "PD1_6") (pintype "bidirectional"))
      (node (ref "Y1") (pin "2") (pinfunction "OSC2_2") (pintype "passive"))
    )
    (net (code "151") (name "Net-(U7-DTR#)") (class "Default")
      (node (ref "R19") (pin "1") (pinfunction "1_1") (pintype "passive"))
      (node (ref "U7") (pin "12") (pinfunction "DTR#_12") (pintype "passive"))
    )
    (net (code "152") (name "Net-(U7-V3.3)") (class "Default")
      (node (ref "C24") (pin "1") (pinfunction "1_1") (pintype "passive"))
      (node (ref "U7") (pin "4") (pinfunction "V3.3_4") (pintype "passive"))
    )
    (net (code "153") (name "Net-(U7-XI)") (class "Default")
      (node (ref "C25") (pin "1") (pinfunction "1_1") (pintype "passive"))
      (node (ref "U7") (pin "7") (pinfunction "XI_7") (pintype "passive"))
      (node (ref "Y2") (pin "1") (pinfunction "OSC1_1") (pintype "passive"))
    )
    (net (code "154") (name "Net-(U7-XO)") (class "Default")
      (node (ref "C26") (pin "1") (pinfunction "1_1") (pintype "passive"))
      (node (ref "U7") (pin "8") (pinfunction "XO_8") (pintype "passive"))
      (node (ref "Y2") (pin "2") (pinfunction "OSC2_2") (pintype "passive"))
    )
    (net (code "155") (name "Net-(U8-QH')") (class "Default")
      (node (ref "U8") (pin "9") (pinfunction "QH'_9") (pintype "output"))
      (node (ref "U9") (pin "14") (pinfunction "SER_14") (pintype "input"))
    )
    (net (code "156") (name "Net-(U10-QH')") (class "Default")
      (node (ref "U10") (pin "9") (pinfunction "QH'_9") (pintype "output"))
      (node (ref "U11") (pin "14") (pinfunction "SER_14") (pintype "input"))
    )
    (net (code "157") (name "Net-(U10-SER)") (class "Default")
      (node (ref "U10") (pin "14") (pinfunction "SER_14") (pintype "input"))
      (node (ref "U9") (pin "9") (pinfunction "QH'_9") (pintype "output"))
    )
    (net (code "158") (name "Net-(U11-QH')") (class "Default")
      (node (ref "U11") (pin "9") (pinfunction "QH'_9") (pintype "output"))
      (node (ref "U12") (pin "14") (pinfunction "SER_14") (pintype "input"))
    )
    (net (code "159") (name "VH") (class "Default")
      (node (ref "C10") (pin "1") (pinfunction "1_1") (pintype "passive"))
      (node (ref "D1") (pin "2") (pinfunction "K_2") (pintype "passive"))
      (node (ref "J2") (pin "1") (pinfunction "1_1") (pintype "passive"))
      (node (ref "R11") (pin "2") (pinfunction "2_2") (pintype "passive"))
      (node (ref "R14") (pin "2") (pinfunction "2_2") (pintype "passive"))
      (node (ref "R15") (pin "2") (pinfunction "2_2") (pintype "passive"))
      (node (ref "R5") (pin "2") (pinfunction "2_2") (pintype "passive"))
      (node (ref "R6") (pin "2") (pinfunction "2_2") (pintype "passive"))
      (node (ref "R7") (pin "2") (pinfunction "2_2") (pintype "passive"))
      (node (ref "R8") (pin "2") (pinfunction "2_2") (pintype "passive"))
    )
    (net (code "160") (name "unconnected-(*1-NC-Pad1)") (class "Default")
      (node (ref "*1") (pin "1") (pinfunction "NC_1") (pintype "passive"))
    )
    (net (code "161") (name "unconnected-(*1-NC-Pad8)") (class "Default")
      (node (ref "*1") (pin "8") (pinfunction "NC_8") (pintype "passive"))
    )
    (net (code "162") (name "unconnected-(*2-NC-Pad1)") (class "Default")
      (node (ref "*2") (pin "1") (pinfunction "NC_1") (pintype "passive"))
    )
    (net (code "163") (name "unconnected-(*2-NC-Pad8)") (class "Default")
      (node (ref "*2") (pin "8") (pinfunction "NC_8") (pintype "passive"))
    )
    (net (code "164") (name "unconnected-(*3-NC-Pad1)") (class "Default")
      (node (ref "*3") (pin "1") (pinfunction "NC_1") (pintype "passive"))
    )
    (net (code "165") (name "unconnected-(*3-NC-Pad8)") (class "Default")
      (node (ref "*3") (pin "8") (pinfunction "NC_8") (pintype "passive"))
    )
    (net (code "166") (name "unconnected-(*4-NC-Pad1)") (class "Default")
      (node (ref "*4") (pin "1") (pinfunction "NC_1") (pintype "passive"))
    )
    (net (code "167") (name "unconnected-(*4-NC-Pad8)") (class "Default")
      (node (ref "*4") (pin "8") (pinfunction "NC_8") (pintype "passive"))
    )
    (net (code "168") (name "unconnected-(Q34-B-Pad1)") (class "Default")
      (node (ref "Q34") (pin "1") (pinfunction "B_1") (pintype "passive"))
    )
    (net (code "169") (name "unconnected-(Q42-B-Pad1)") (class "Default")
      (node (ref "Q42") (pin "1") (pinfunction "B_1") (pintype "passive"))
    )
    (net (code "170") (name "unconnected-(T1-Pad1)") (class "Default")
      (node (ref "T1") (pin "1") (pinfunction "1_1") (pintype "passive"))
    )
    (net (code "171") (name "unconnected-(T2-Pad1)") (class "Default")
      (node (ref "T2") (pin "1") (pinfunction "1_1") (pintype "passive"))
    )
    (net (code "172") (name "unconnected-(T3-Pad1)") (class "Default")
      (node (ref "T3") (pin "1") (pinfunction "1_1") (pintype "passive"))
    )
    (net (code "173") (name "unconnected-(T4-Pad1)") (class "Default")
      (node (ref "T4") (pin "1") (pinfunction "1_1") (pintype "passive"))
    )
    (net (code "174") (name "unconnected-(U4-DO-Pad2)") (class "Default")
      (node (ref "U4") (pin "2") (pinfunction "DO_2") (pintype "passive"))
    )
    (net (code "175") (name "unconnected-(U6A-PA0-WKUP-Pad14)") (class "Default")
      (node (ref "U6") (pin "14") (pinfunction "PA0-WKUP_14") (pintype "bidirectional"))
    )
    (net (code "176") (name "unconnected-(U6A-PA3-Pad17)") (class "Default")
      (node (ref "U6") (pin "17") (pinfunction "PA3_17") (pintype "bidirectional"))
    )
    (net (code "177") (name "unconnected-(U6A-PA4-Pad20)") (class "Default")
      (node (ref "U6") (pin "20") (pinfunction "PA4_20") (pintype "bidirectional"))
    )
    (net (code "178") (name "unconnected-(U6A-PA5-Pad21)") (class "Default")
      (node (ref "U6") (pin "21") (pinfunction "PA5_21") (pintype "bidirectional"))
    )
    (net (code "179") (name "unconnected-(U6A-PA8-Pad41)") (class "Default")
      (node (ref "U6") (pin "41") (pinfunction "PA8_41") (pintype "bidirectional"))
    )
    (net (code "180") (name "unconnected-(U6A-PA11-Pad44)") (class "Default")
      (node (ref "U6") (pin "44") (pinfunction "PA11_44") (pintype "bidirectional"))
    )
    (net (code "181") (name "unconnected-(U6A-PA12-Pad45)") (class "Default")
      (node (ref "U6") (pin "45") (pinfunction "PA12_45") (pintype "bidirectional"))
    )
    (net (code "182") (name "unconnected-(U6A-PA15-Pad50)") (class "Default")
      (node (ref "U6") (pin "50") (pinfunction "PA15_50") (pintype "bidirectional"))
    )
    (net (code "183") (name "unconnected-(U6A-PB3-Pad55)") (class "Default")
      (node (ref "U6") (pin "55") (pinfunction "PB3_55") (pintype "bidirectional"))
    )
    (net (code "184") (name "unconnected-(U6A-PB5-Pad57)") (class "Default")
      (node (ref "U6") (pin "57") (pinfunction "PB5_57") (pintype "bidirectional"))
    )
    (net (code "185") (name "unconnected-(U6A-PB7-Pad59)") (class "Default")
      (node (ref "U6") (pin "59") (pinfunction "PB7_59") (pintype "bidirectional"))
    )
    (net (code "186") (name "unconnected-(U6A-PB10-Pad29)") (class "Default")
      (node (ref "U6") (pin "29") (pinfunction "PB10_29") (pintype "bidirectional"))
    )
    (net (code "187") (name "unconnected-(U6A-PB11-Pad30)") (class "Default")
      (node (ref "U6") (pin "30") (pinfunction "PB11_30") (pintype "bidirectional"))
    )
    (net (code "188") (name "unconnected-(U6A-PB12-Pad33)") (class "Default")
      (node (ref "U6") (pin "33") (pinfunction "PB12_33") (pintype "bidirectional"))
    )
    (net (code "189") (name "unconnected-(U6A-PB13-Pad34)") (class "Default")
      (node (ref "U6") (pin "34") (pinfunction "PB13_34") (pintype "bidirectional"))
    )
    (net (code "190") (name "unconnected-(U6A-PB14-Pad35)") (class "Default")
      (node (ref "U6") (pin "35") (pinfunction "PB14_35") (pintype "bidirectional"))
    )
    (net (code "191") (name "unconnected-(U6A-PC7-Pad38)") (class "Default")
      (node (ref "U6") (pin "38") (pinfunction "PC7_38") (pintype "bidirectional"))
    )
    (net (code "192") (name "unconnected-(U6A-PC12-Pad53)") (class "Default")
      (node (ref "U6") (pin "53") (pinfunction "PC12_53") (pintype "bidirectional"))
    )
    (net (code "193") (name "unconnected-(U6A-PC13-TAMPER-RTC-Pad2)") (class "Default")
      (node (ref "U6") (pin "2") (pinfunction "PC13-TAMPER-RTC_2") (pintype "bidirectional"))
    )
    (net (code "194") (name "unconnected-(U6A-PC14-OSC32_IN-Pad3)") (class "Default")
      (node (ref "U6") (pin "3") (pinfunction "PC14-OSC32_IN_3") (pintype "bidirectional"))
    )
    (net (code "195") (name "unconnected-(U6A-PC15-OSC32_OUT-Pad4)") (class "Default")
      (node (ref "U6") (pin "4") (pinfunction "PC15-OSC32_OUT_4") (pintype "bidirectional"))
    )
    (net (code "196") (name "unconnected-(U6A-PD2-Pad54)") (class "Default")
      (node (ref "U6") (pin "54") (pinfunction "PD2_54") (pintype "bidirectional"))
    )
    (net (code "197") (name "unconnected-(U7-CTS#-Pad9)") (class "Default")
      (node (ref "U7") (pin "9") (pinfunction "CTS#_9") (pintype "passive"))
    )
    (net (code "198") (name "unconnected-(U7-DCD#-Pad13)") (class "Default")
      (node (ref "U7") (pin "13") (pinfunction "DCD#_13") (pintype "passive"))
    )
    (net (code "199") (name "unconnected-(U7-DSR#-Pad15)") (class "Default")
      (node (ref "U7") (pin "15") (pinfunction "DSR#_15") (pintype "passive"))
    )
    (net (code "200") (name "unconnected-(U7-R232-Pad10)") (class "Default")
      (node (ref "U7") (pin "10") (pinfunction "R232_10") (pintype "passive"))
    )
    (net (code "201") (name "unconnected-(U7-RI#-Pad14)") (class "Default")
      (node (ref "U7") (pin "14") (pinfunction "RI#_14") (pintype "passive"))
    )
    (net (code "202") (name "unconnected-(U12-QH'-Pad9)") (class "Default")
      (node (ref "U12") (pin "9") (pinfunction "QH'_9") (pintype "output"))
    )
    (net (code "203") (name "unconnected-(U14-32KHZ-Pad1)") (class "Default")
      (node (ref "U14") (pin "1") (pinfunction "32KHZ_1") (pintype "passive"))
    )
    (net (code "204") (name "unconnected-(U14-~{RST}-Pad4)") (class "Default")
      (node (ref "U14") (pin "4") (pinfunction "~{RST}_4") (pintype "passive"))
    )
  )
)
